# homeboard12.net
KiCad netlist of a schematic drawn in EAGLE
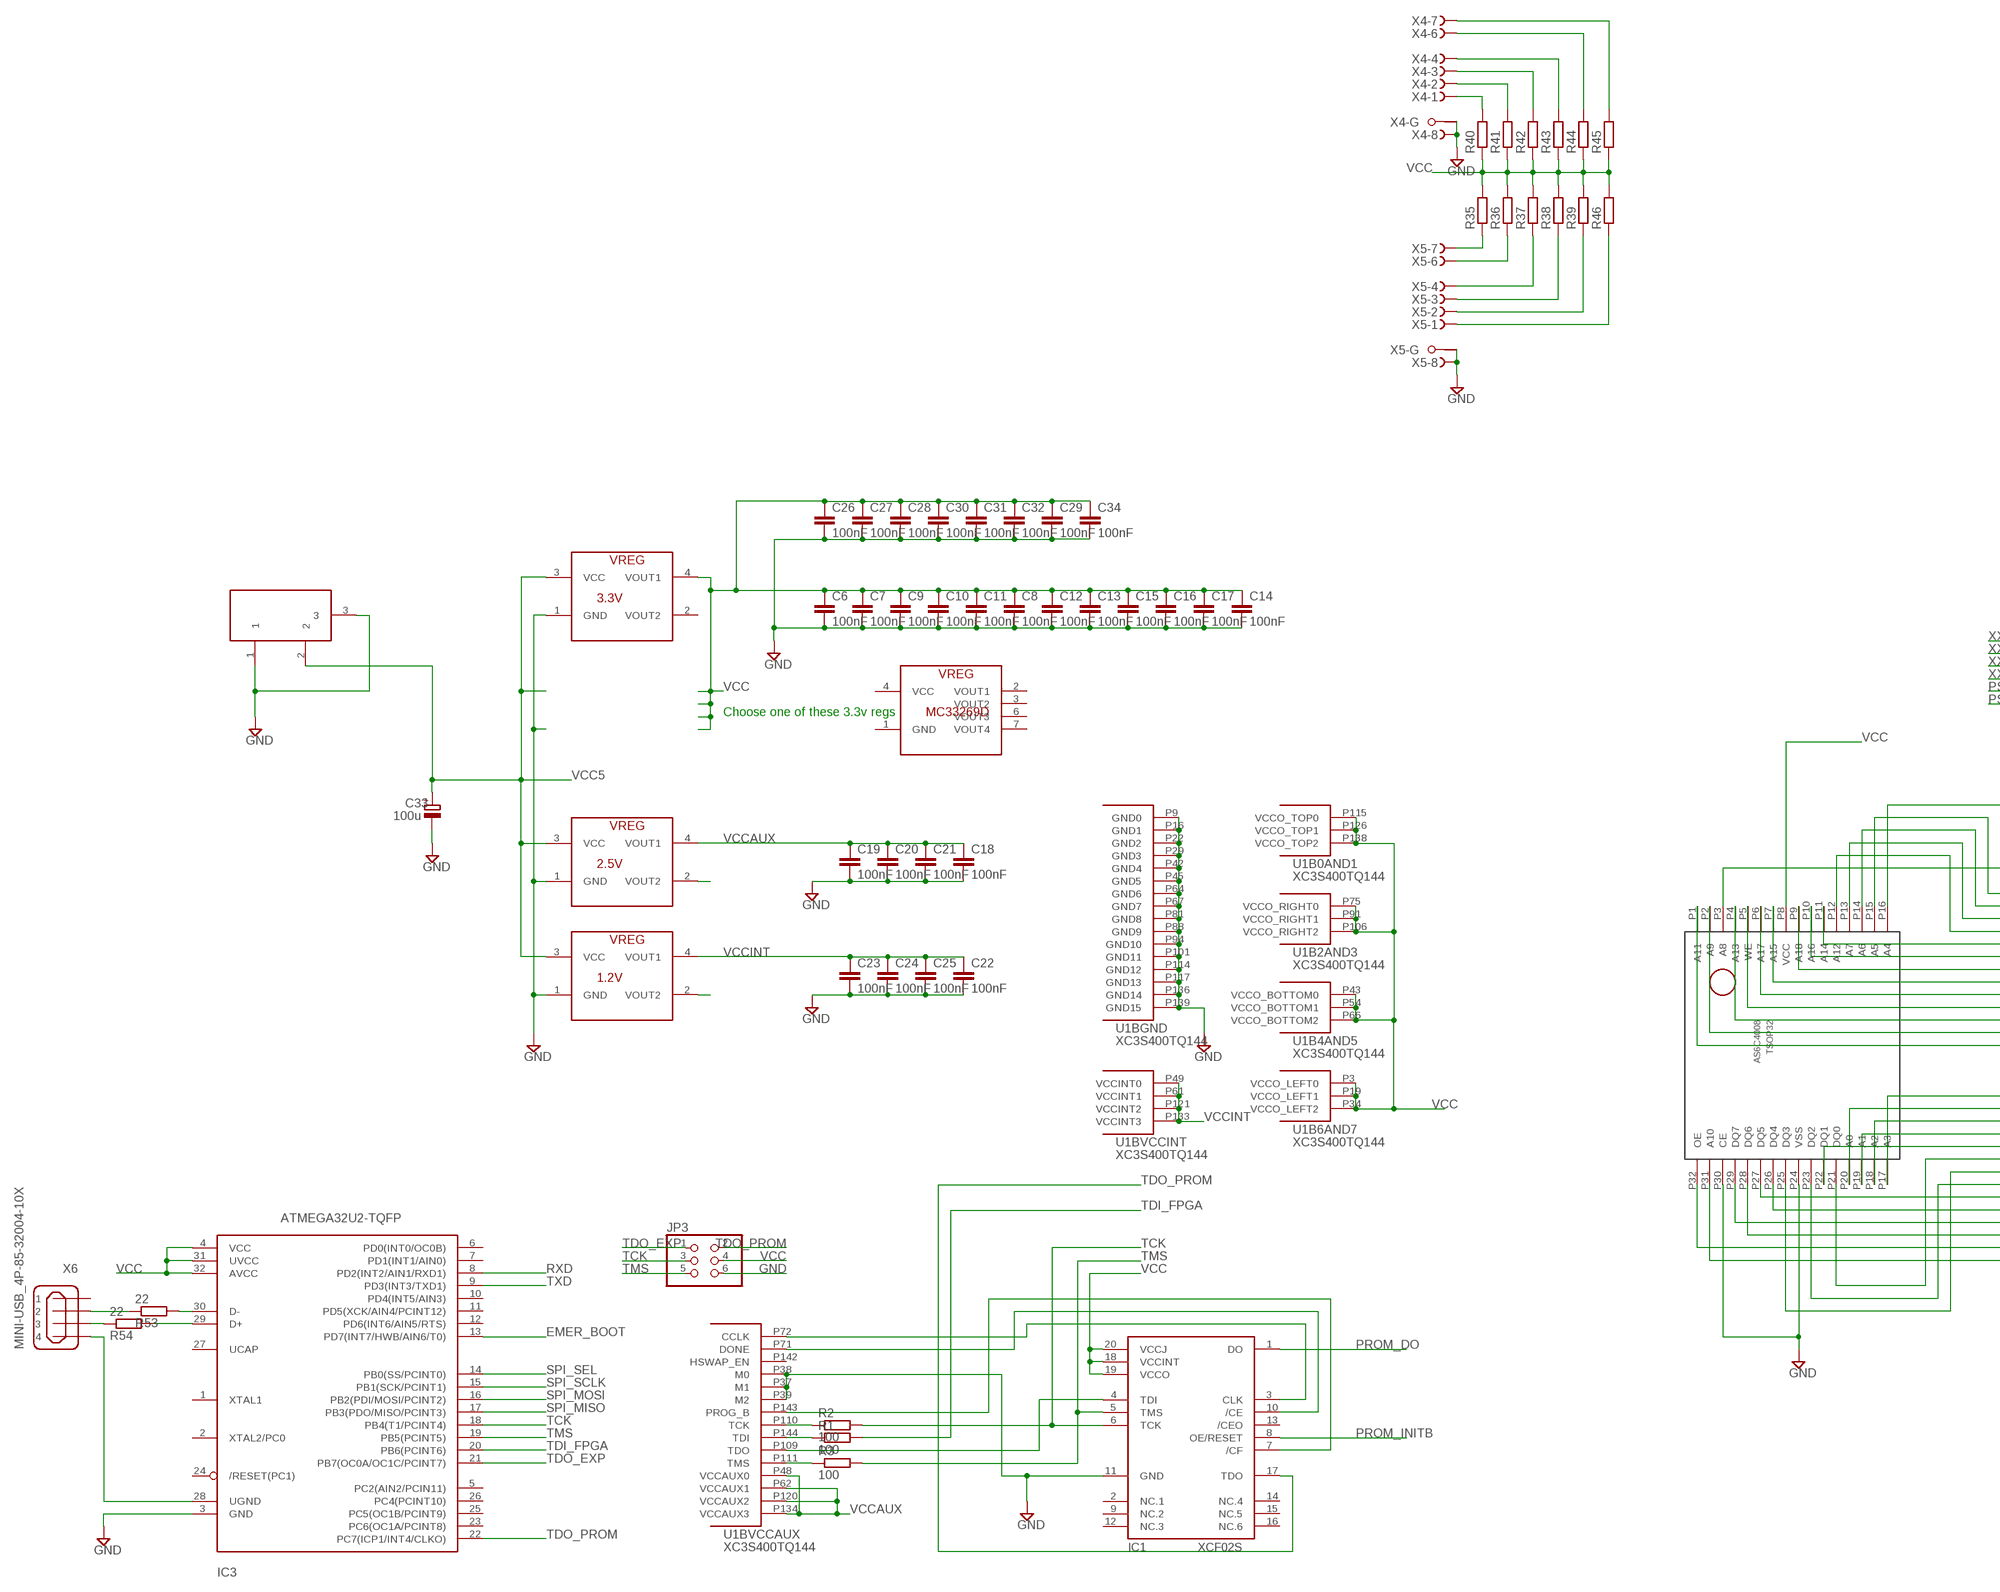
[diagram p0: schematic, sheet 1, part 1 of 3]
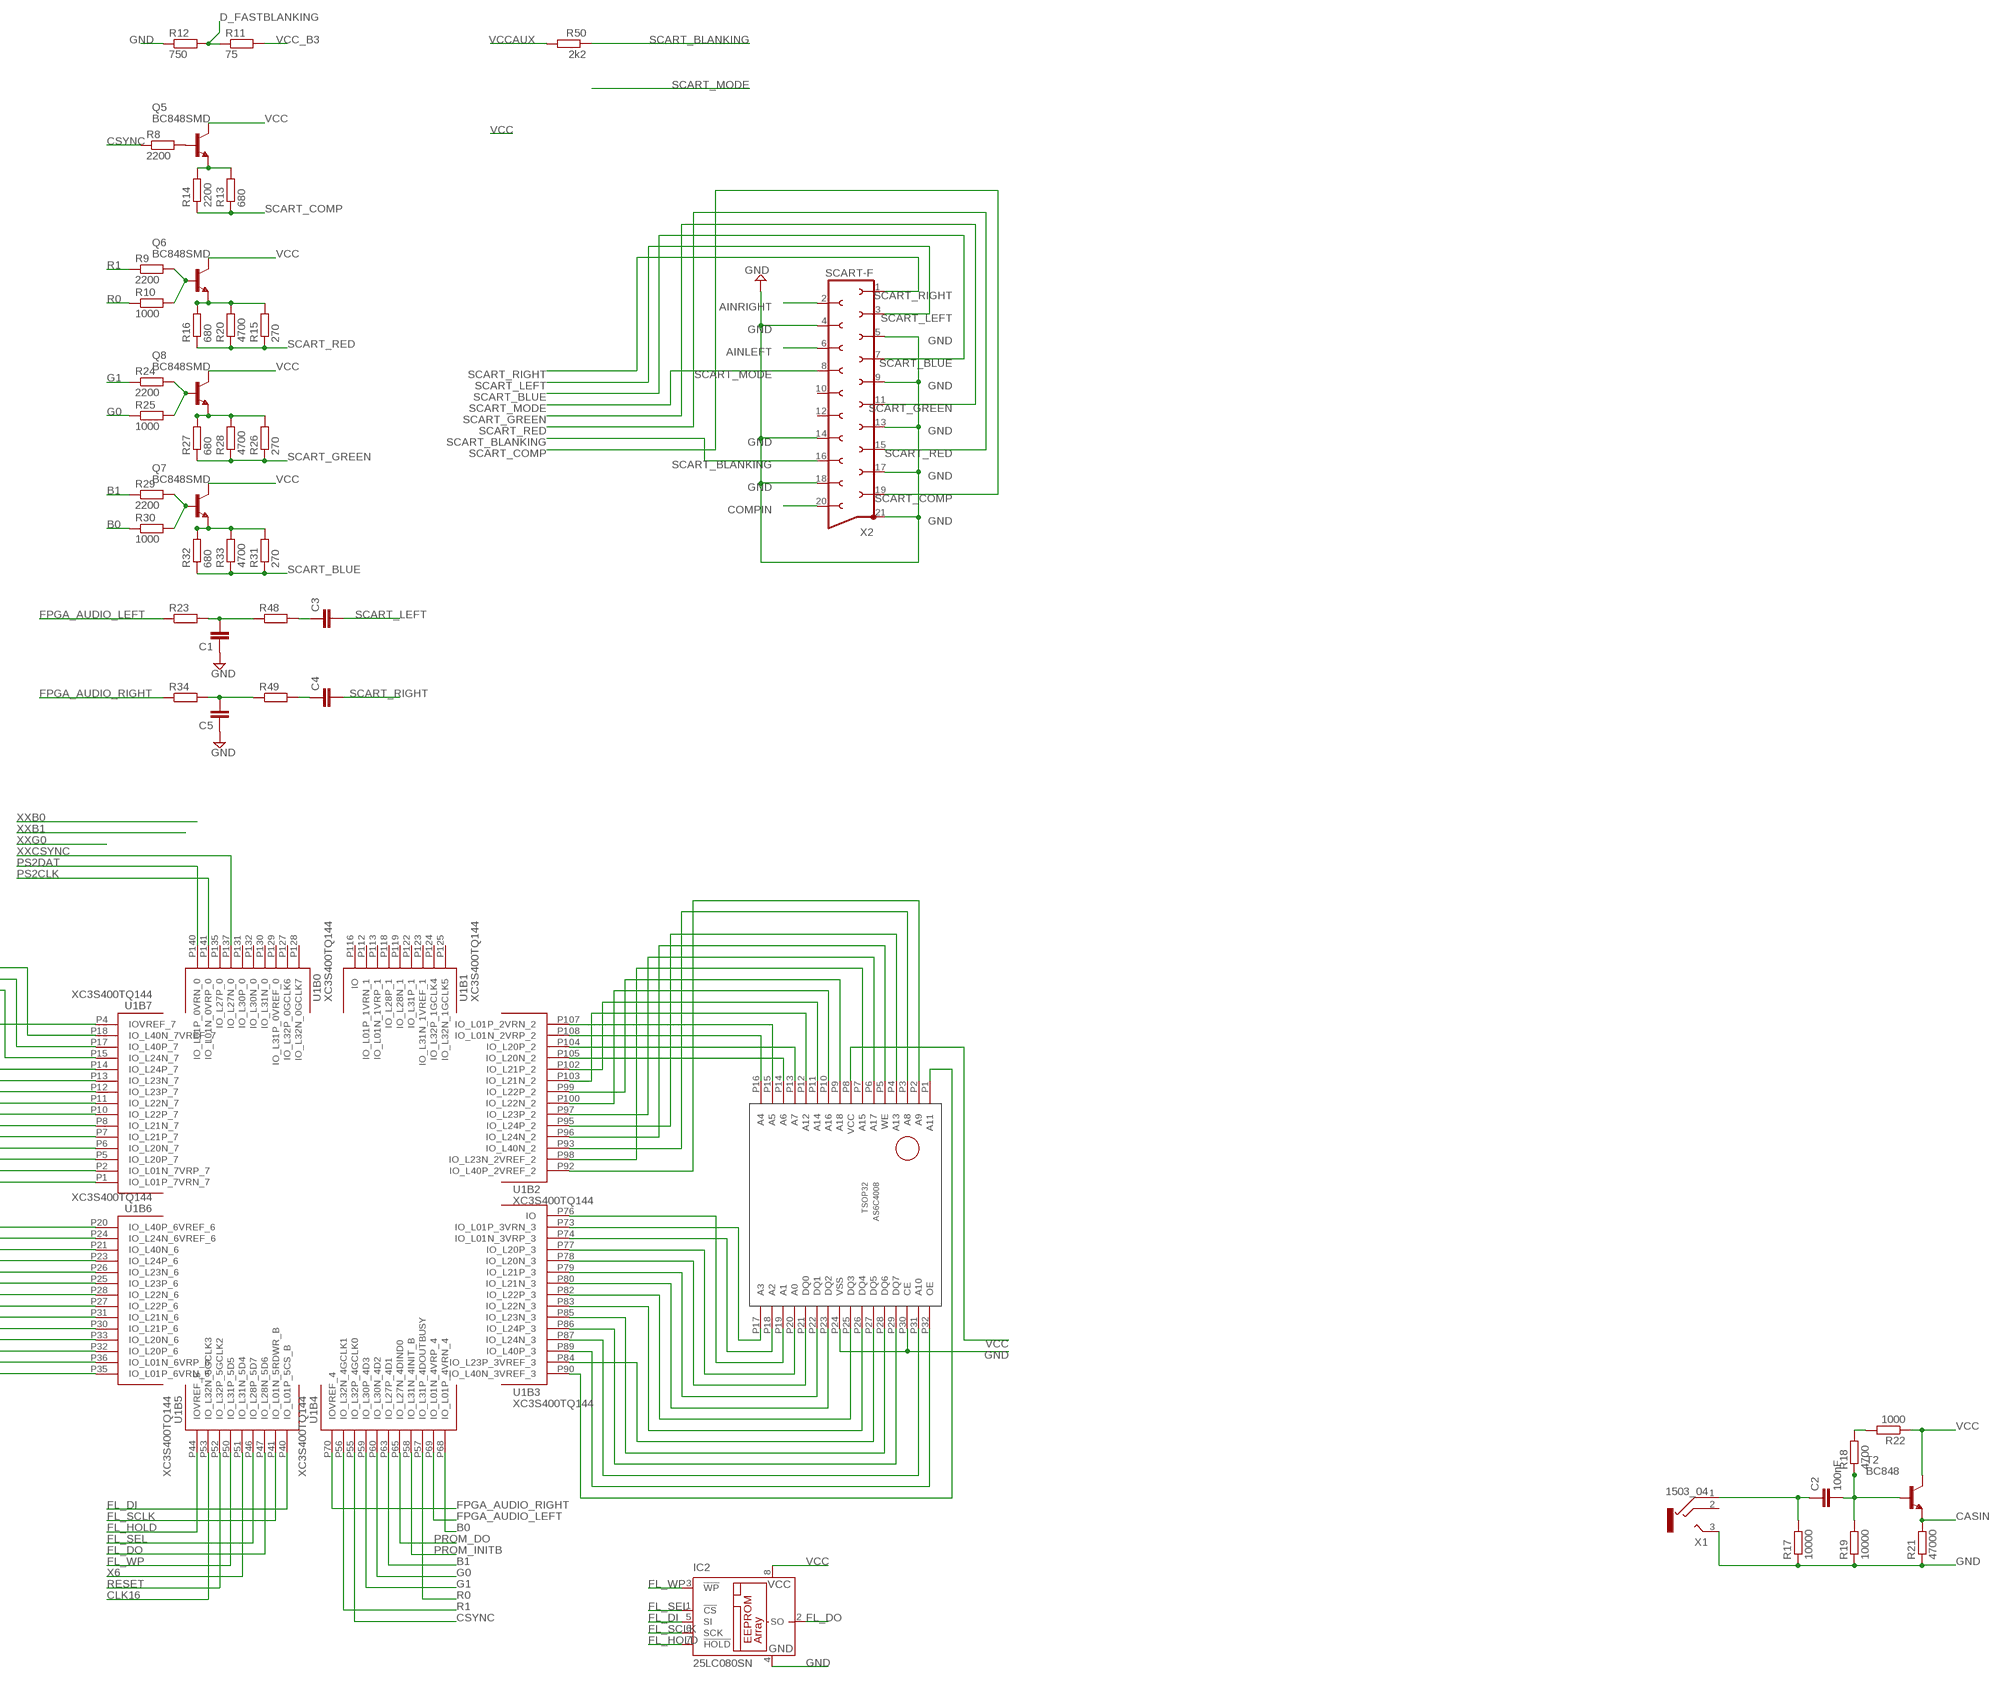
[diagram p1: schematic, sheet 1, part 2 of 3]
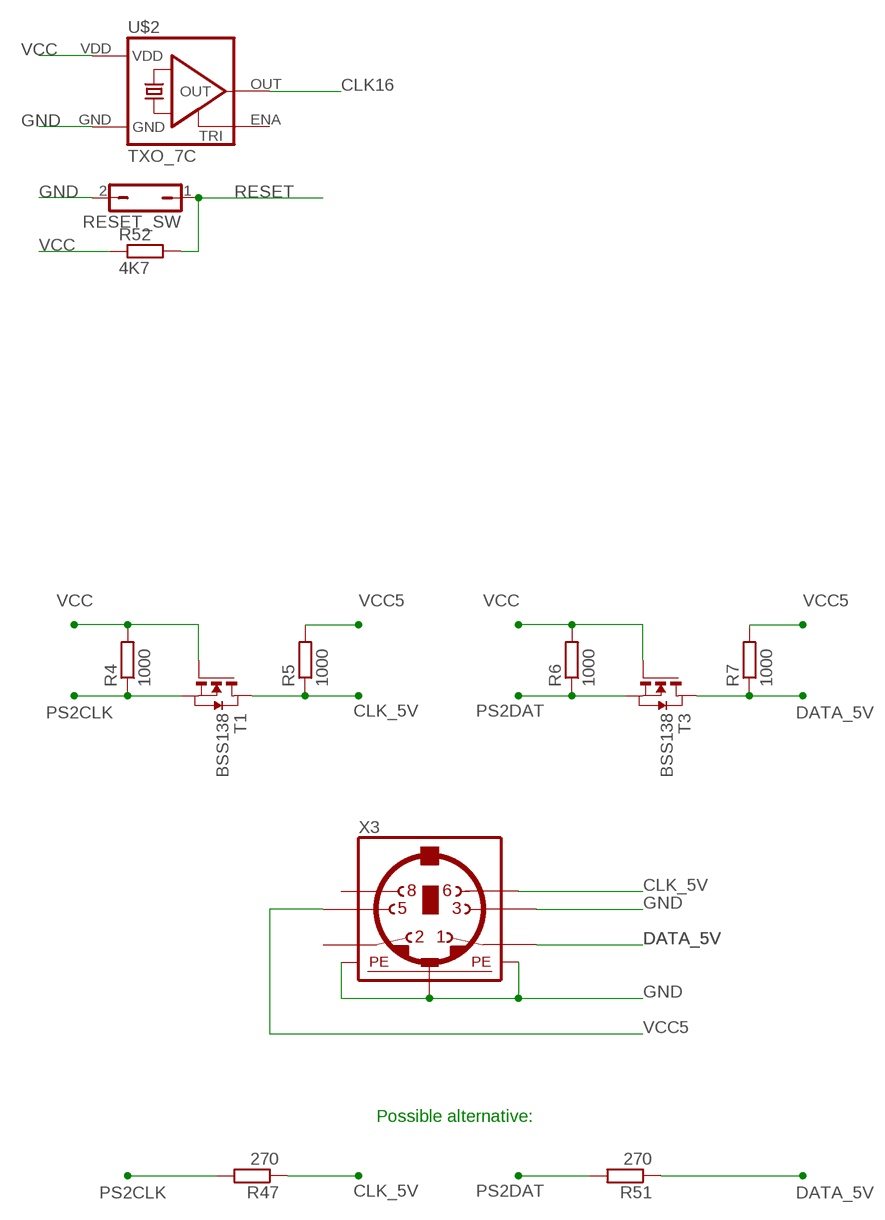
[diagram p2: schematic, sheet 1, part 3 of 3]

(export (version "E")
  (design (tool "Eeschema 10.0.6"))
  (components
    (comp (ref "C1")
      (value "C-EUC0603")
      (footprint "eagle-import:C0603")
      (libsource (lib "eagle-import") (part "resistor_C-EUC0603"))
    )
    (comp (ref "C2")
      (value "100nF")
      (footprint "eagle-import:C0603")
      (libsource (lib "eagle-import") (part "resistor_C-EUC0603"))
    )
    (comp (ref "C3")
      (value "C-EUC0603")
      (footprint "eagle-import:C0603")
      (libsource (lib "eagle-import") (part "resistor_C-EUC0603"))
    )
    (comp (ref "C4")
      (value "C-EUC0603")
      (footprint "eagle-import:C0603")
      (libsource (lib "eagle-import") (part "resistor_C-EUC0603"))
    )
    (comp (ref "C5")
      (value "C-EUC0603")
      (footprint "eagle-import:C0603")
      (libsource (lib "eagle-import") (part "resistor_C-EUC0603"))
    )
    (comp (ref "C6")
      (value "100nF")
      (footprint "eagle-import:C0603")
      (libsource (lib "eagle-import") (part "C-EUC0603"))
    )
    (comp (ref "C7")
      (value "100nF")
      (footprint "eagle-import:C0603")
      (libsource (lib "eagle-import") (part "C-EUC0603"))
    )
    (comp (ref "C8")
      (value "100nF")
      (footprint "eagle-import:C0603")
      (libsource (lib "eagle-import") (part "C-EUC0603"))
    )
    (comp (ref "C9")
      (value "100nF")
      (footprint "eagle-import:C0603")
      (libsource (lib "eagle-import") (part "C-EUC0603"))
    )
    (comp (ref "C10")
      (value "100nF")
      (footprint "eagle-import:C0603")
      (libsource (lib "eagle-import") (part "C-EUC0603"))
    )
    (comp (ref "C11")
      (value "100nF")
      (footprint "eagle-import:C0603")
      (libsource (lib "eagle-import") (part "C-EUC0603"))
    )
    (comp (ref "C12")
      (value "100nF")
      (footprint "eagle-import:C0603")
      (libsource (lib "eagle-import") (part "C-EUC0603"))
    )
    (comp (ref "C13")
      (value "100nF")
      (footprint "eagle-import:C0603")
      (libsource (lib "eagle-import") (part "C-EUC0603"))
    )
    (comp (ref "C14")
      (value "100nF")
      (footprint "eagle-import:C0603")
      (libsource (lib "eagle-import") (part "C-EUC0603"))
    )
    (comp (ref "C15")
      (value "100nF")
      (footprint "eagle-import:C0603")
      (libsource (lib "eagle-import") (part "C-EUC0603"))
    )
    (comp (ref "C16")
      (value "100nF")
      (footprint "eagle-import:C0603")
      (libsource (lib "eagle-import") (part "C-EUC0603"))
    )
    (comp (ref "C17")
      (value "100nF")
      (footprint "eagle-import:C0603")
      (libsource (lib "eagle-import") (part "C-EUC0603"))
    )
    (comp (ref "C18")
      (value "100nF")
      (footprint "eagle-import:C0603")
      (libsource (lib "eagle-import") (part "C-EUC0603"))
    )
    (comp (ref "C19")
      (value "100nF")
      (footprint "eagle-import:C0603")
      (libsource (lib "eagle-import") (part "C-EUC0603"))
    )
    (comp (ref "C20")
      (value "100nF")
      (footprint "eagle-import:C0603")
      (libsource (lib "eagle-import") (part "C-EUC0603"))
    )
    (comp (ref "C21")
      (value "100nF")
      (footprint "eagle-import:C0603")
      (libsource (lib "eagle-import") (part "C-EUC0603"))
    )
    (comp (ref "C22")
      (value "100nF")
      (footprint "eagle-import:C0603")
      (libsource (lib "eagle-import") (part "C-EUC0603"))
    )
    (comp (ref "C23")
      (value "100nF")
      (footprint "eagle-import:C0603")
      (libsource (lib "eagle-import") (part "C-EUC0603"))
    )
    (comp (ref "C24")
      (value "100nF")
      (footprint "eagle-import:C0603")
      (libsource (lib "eagle-import") (part "C-EUC0603"))
    )
    (comp (ref "C25")
      (value "100nF")
      (footprint "eagle-import:C0603")
      (libsource (lib "eagle-import") (part "C-EUC0603"))
    )
    (comp (ref "C26")
      (value "100nF")
      (footprint "eagle-import:C0603")
      (libsource (lib "eagle-import") (part "C-EUC0603"))
    )
    (comp (ref "C27")
      (value "100nF")
      (footprint "eagle-import:C0603")
      (libsource (lib "eagle-import") (part "C-EUC0603"))
    )
    (comp (ref "C28")
      (value "100nF")
      (footprint "eagle-import:C0603")
      (libsource (lib "eagle-import") (part "C-EUC0603"))
    )
    (comp (ref "C29")
      (value "100nF")
      (footprint "eagle-import:C0603")
      (libsource (lib "eagle-import") (part "C-EUC0603"))
    )
    (comp (ref "C30")
      (value "100nF")
      (footprint "eagle-import:C0603")
      (libsource (lib "eagle-import") (part "C-EUC0603"))
    )
    (comp (ref "C31")
      (value "100nF")
      (footprint "eagle-import:C0603")
      (libsource (lib "eagle-import") (part "C-EUC0603"))
    )
    (comp (ref "C32")
      (value "100nF")
      (footprint "eagle-import:C0603")
      (libsource (lib "eagle-import") (part "C-EUC0603"))
    )
    (comp (ref "C33")
      (value "100u")
      (footprint "eagle-import:PANASONIC_D")
      (libsource (lib "eagle-import") (part "CPOL-EUD"))
    )
    (comp (ref "C34")
      (value "100nF")
      (footprint "eagle-import:C0603")
      (libsource (lib "eagle-import") (part "C-EUC0603"))
    )
    (comp (ref "IC1")
      (value "XCF02S")
      (footprint "eagle-import:VO20")
      (libsource (lib "eagle-import") (part "XCF02S"))
    )
    (comp (ref "IC2")
      (value "25LC080SN")
      (footprint "eagle-import:SO-08")
      (fields (field (name "MF") "MICROCHIP") (field (name "MPN") "25LC080/SN"))
      (libsource (lib "eagle-import") (part "25SNLC080"))
    )
    (comp (ref "IC3")
      (value "ATMEGA32U2-TQFP")
      (footprint "eagle-import:TQFP32-08")
      (libsource (lib "eagle-import") (part "ATMEGA32U2-TQFP"))
    )
    (comp (ref "JP3")
      (value "PINHD-2X3")
      (footprint "eagle-import:2X03")
      (libsource (lib "eagle-import") (part "PINHD-2X3"))
    )
    (comp (ref "Q5")
      (value "BC848SMD")
      (footprint "eagle-import:SOT23")
      (libsource (lib "eagle-import") (part "BC848SMD"))
    )
    (comp (ref "Q6")
      (value "BC848SMD")
      (footprint "eagle-import:SOT23")
      (libsource (lib "eagle-import") (part "BC848SMD"))
    )
    (comp (ref "Q7")
      (value "BC848SMD")
      (footprint "eagle-import:SOT23")
      (libsource (lib "eagle-import") (part "BC848SMD"))
    )
    (comp (ref "Q8")
      (value "BC848SMD")
      (footprint "eagle-import:SOT23")
      (libsource (lib "eagle-import") (part "BC848SMD"))
    )
    (comp (ref "R1")
      (value "100")
      (footprint "eagle-import:R0805")
      (libsource (lib "eagle-import") (part "R-EU_R0805"))
    )
    (comp (ref "R2")
      (value "100")
      (footprint "eagle-import:R0805")
      (libsource (lib "eagle-import") (part "R-EU_R0805"))
    )
    (comp (ref "R3")
      (value "100")
      (footprint "eagle-import:R0805")
      (libsource (lib "eagle-import") (part "R-EU_R0805"))
    )
    (comp (ref "R4")
      (value "1000")
      (footprint "eagle-import:R0805")
      (libsource (lib "eagle-import") (part "R-EU_R0805"))
    )
    (comp (ref "R5")
      (value "1000")
      (footprint "eagle-import:R0805")
      (libsource (lib "eagle-import") (part "R-EU_R0805"))
    )
    (comp (ref "R6")
      (value "1000")
      (footprint "eagle-import:R0805")
      (libsource (lib "eagle-import") (part "R-EU_R0805"))
    )
    (comp (ref "R7")
      (value "1000")
      (footprint "eagle-import:R0805")
      (libsource (lib "eagle-import") (part "R-EU_R0805"))
    )
    (comp (ref "R8")
      (value "2200")
      (footprint "eagle-import:R0805")
      (libsource (lib "eagle-import") (part "R-EU_R0805"))
    )
    (comp (ref "R9")
      (value "2200")
      (footprint "eagle-import:R0805")
      (libsource (lib "eagle-import") (part "R-EU_R0805"))
    )
    (comp (ref "R10")
      (value "1000")
      (footprint "eagle-import:R0805")
      (libsource (lib "eagle-import") (part "R-EU_R0805"))
    )
    (comp (ref "R11")
      (value "75")
      (footprint "eagle-import:R0805")
      (libsource (lib "eagle-import") (part "R-EU_R0805"))
    )
    (comp (ref "R12")
      (value "750")
      (footprint "eagle-import:R0805")
      (libsource (lib "eagle-import") (part "R-EU_R0805"))
    )
    (comp (ref "R13")
      (value "680")
      (footprint "eagle-import:R0805")
      (libsource (lib "eagle-import") (part "R-EU_R0805"))
    )
    (comp (ref "R14")
      (value "2200")
      (footprint "eagle-import:R0805")
      (libsource (lib "eagle-import") (part "R-EU_R0805"))
    )
    (comp (ref "R15")
      (value "270")
      (footprint "eagle-import:R0805")
      (libsource (lib "eagle-import") (part "R-EU_R0805"))
    )
    (comp (ref "R16")
      (value "680")
      (footprint "eagle-import:R0805")
      (libsource (lib "eagle-import") (part "R-EU_R0805"))
    )
    (comp (ref "R17")
      (value "10000")
      (footprint "eagle-import:R0805")
      (libsource (lib "eagle-import") (part "R-EU_R0805"))
    )
    (comp (ref "R18")
      (value "4700")
      (footprint "eagle-import:R0805")
      (libsource (lib "eagle-import") (part "R-EU_R0805"))
    )
    (comp (ref "R19")
      (value "10000")
      (footprint "eagle-import:R0805")
      (libsource (lib "eagle-import") (part "R-EU_R0805"))
    )
    (comp (ref "R20")
      (value "4700")
      (footprint "eagle-import:R0805")
      (libsource (lib "eagle-import") (part "R-EU_R0805"))
    )
    (comp (ref "R21")
      (value "47000")
      (footprint "eagle-import:R0805")
      (libsource (lib "eagle-import") (part "R-EU_R0805"))
    )
    (comp (ref "R22")
      (value "1000")
      (footprint "eagle-import:R0805")
      (libsource (lib "eagle-import") (part "R-EU_R0805"))
    )
    (comp (ref "R23")
      (value "R-EU_M0805")
      (footprint "eagle-import:M0805")
      (libsource (lib "eagle-import") (part "resistor_R-EU_M0805"))
    )
    (comp (ref "R24")
      (value "2200")
      (footprint "eagle-import:R0805")
      (libsource (lib "eagle-import") (part "R-EU_R0805"))
    )
    (comp (ref "R25")
      (value "1000")
      (footprint "eagle-import:R0805")
      (libsource (lib "eagle-import") (part "R-EU_R0805"))
    )
    (comp (ref "R26")
      (value "270")
      (footprint "eagle-import:R0805")
      (libsource (lib "eagle-import") (part "R-EU_R0805"))
    )
    (comp (ref "R27")
      (value "680")
      (footprint "eagle-import:R0805")
      (libsource (lib "eagle-import") (part "R-EU_R0805"))
    )
    (comp (ref "R28")
      (value "4700")
      (footprint "eagle-import:R0805")
      (libsource (lib "eagle-import") (part "R-EU_R0805"))
    )
    (comp (ref "R29")
      (value "2200")
      (footprint "eagle-import:R0805")
      (libsource (lib "eagle-import") (part "R-EU_R0805"))
    )
    (comp (ref "R30")
      (value "1000")
      (footprint "eagle-import:R0805")
      (libsource (lib "eagle-import") (part "R-EU_R0805"))
    )
    (comp (ref "R31")
      (value "270")
      (footprint "eagle-import:R0805")
      (libsource (lib "eagle-import") (part "R-EU_R0805"))
    )
    (comp (ref "R32")
      (value "680")
      (footprint "eagle-import:R0805")
      (libsource (lib "eagle-import") (part "R-EU_R0805"))
    )
    (comp (ref "R33")
      (value "4700")
      (footprint "eagle-import:R0805")
      (libsource (lib "eagle-import") (part "R-EU_R0805"))
    )
    (comp (ref "R34")
      (value "R-EU_M0805")
      (footprint "eagle-import:M0805")
      (libsource (lib "eagle-import") (part "resistor_R-EU_M0805"))
    )
    (comp (ref "R35")
      (value "R-EU_M0805")
      (footprint "eagle-import:M0805")
      (libsource (lib "eagle-import") (part "resistor_R-EU_M0805"))
    )
    (comp (ref "R36")
      (value "R-EU_M0805")
      (footprint "eagle-import:M0805")
      (libsource (lib "eagle-import") (part "resistor_R-EU_M0805"))
    )
    (comp (ref "R37")
      (value "R-EU_M0805")
      (footprint "eagle-import:M0805")
      (libsource (lib "eagle-import") (part "resistor_R-EU_M0805"))
    )
    (comp (ref "R38")
      (value "R-EU_M0805")
      (footprint "eagle-import:M0805")
      (libsource (lib "eagle-import") (part "resistor_R-EU_M0805"))
    )
    (comp (ref "R39")
      (value "R-EU_M0805")
      (footprint "eagle-import:M0805")
      (libsource (lib "eagle-import") (part "resistor_R-EU_M0805"))
    )
    (comp (ref "R40")
      (value "R-EU_M0805")
      (footprint "eagle-import:M0805")
      (libsource (lib "eagle-import") (part "resistor_R-EU_M0805"))
    )
    (comp (ref "R41")
      (value "R-EU_M0805")
      (footprint "eagle-import:M0805")
      (libsource (lib "eagle-import") (part "resistor_R-EU_M0805"))
    )
    (comp (ref "R42")
      (value "R-EU_M0805")
      (footprint "eagle-import:M0805")
      (libsource (lib "eagle-import") (part "resistor_R-EU_M0805"))
    )
    (comp (ref "R43")
      (value "R-EU_M0805")
      (footprint "eagle-import:M0805")
      (libsource (lib "eagle-import") (part "resistor_R-EU_M0805"))
    )
    (comp (ref "R44")
      (value "R-EU_M0805")
      (footprint "eagle-import:M0805")
      (libsource (lib "eagle-import") (part "resistor_R-EU_M0805"))
    )
    (comp (ref "R45")
      (value "R-EU_M0805")
      (footprint "eagle-import:M0805")
      (libsource (lib "eagle-import") (part "resistor_R-EU_M0805"))
    )
    (comp (ref "R46")
      (value "R-EU_M0805")
      (footprint "eagle-import:M0805")
      (libsource (lib "eagle-import") (part "resistor_R-EU_M0805"))
    )
    (comp (ref "R47")
      (value "270")
      (footprint "eagle-import:R0805")
      (libsource (lib "eagle-import") (part "R-EU_R0805"))
    )
    (comp (ref "R48")
      (value "R-EU_M0805")
      (footprint "eagle-import:M0805")
      (libsource (lib "eagle-import") (part "resistor_R-EU_M0805"))
    )
    (comp (ref "R49")
      (value "R-EU_M0805")
      (footprint "eagle-import:M0805")
      (libsource (lib "eagle-import") (part "resistor_R-EU_M0805"))
    )
    (comp (ref "R50")
      (value "2k2")
      (footprint "eagle-import:M0805")
      (libsource (lib "eagle-import") (part "resistor_R-EU_M0805"))
    )
    (comp (ref "R51")
      (value "270")
      (footprint "eagle-import:R0805")
      (libsource (lib "eagle-import") (part "R-EU_R0805"))
    )
    (comp (ref "R52")
      (value "4K7")
      (footprint "eagle-import:M0805")
      (libsource (lib "eagle-import") (part "resistor_R-EU_M0805"))
    )
    (comp (ref "R53")
      (value "22")
      (footprint "eagle-import:R0805")
      (libsource (lib "eagle-import") (part "R-EU_R0805"))
    )
    (comp (ref "R54")
      (value "22")
      (footprint "eagle-import:R0805")
      (libsource (lib "eagle-import") (part "R-EU_R0805"))
    )
    (comp (ref "REG1.2")
      (value "1.2V")
      (footprint "eagle-import:SOT223")
      (libsource (lib "eagle-import") (part "NX1117"))
    )
    (comp (ref "REG2.5")
      (value "2.5V")
      (footprint "eagle-import:SOT223")
      (libsource (lib "eagle-import") (part "NX1117"))
    )
    (comp (ref "RESET_SW")
      (value "JP1Q")
      (footprint "eagle-import:JP1")
      (libsource (lib "eagle-import") (part "JP1Q"))
    )
    (comp (ref "T1")
      (value "BSS138")
      (footprint "eagle-import:SOT-23")
      (libsource (lib "eagle-import") (part "NMOSSOT23"))
    )
    (comp (ref "T2")
      (value "BC848")
      (footprint "eagle-import:SOT23")
      (libsource (lib "eagle-import") (part "BC848"))
    )
    (comp (ref "T3")
      (value "BSS138")
      (footprint "eagle-import:SOT-23")
      (libsource (lib "eagle-import") (part "NMOSSOT23"))
    )
    (comp (ref "U$1")
      (value "AS6C4008")
      (footprint "eagle-import:TSOP32")
      (libsource (lib "eagle-import") (part "AS6C4008"))
    )
    (comp (ref "U$2")
      (value "TXO_7C")
      (footprint "eagle-import:OSC_7C")
      (libsource (lib "eagle-import") (part "TXO_7C"))
    )
    (comp (ref "U$4")
      (value "3.3V")
      (footprint "eagle-import:SOT223")
      (libsource (lib "eagle-import") (part "NX1117"))
    )
    (comp (ref "U$5")
      (value "MC33269D")
      (footprint "eagle-import:SO8")
      (libsource (lib "eagle-import") (part "MC33269D"))
    )
    (comp (ref "U$6")
      (value "AS6C4008")
      (footprint "eagle-import:TSOP32")
      (libsource (lib "eagle-import") (part "AS6C4008"))
    )
    (comp (ref "U1")
      (value "XC3S400TQ144")
      (footprint "eagle-import:TQ144")
      (libsource (lib "eagle-import") (part "XC3S400TQ144"))
    )
    (comp (ref "X1")
      (value "1503_04")
      (footprint "eagle-import:1503_04")
      (libsource (lib "eagle-import") (part "1503_04"))
    )
    (comp (ref "X2")
      (value "SCART-F")
      (footprint "eagle-import:SCART-F")
      (libsource (lib "eagle-import") (part "SCART-F"))
    )
    (comp (ref "X3")
      (value "MINI_DIN_6")
      (footprint "eagle-import:M_DIN6")
      (libsource (lib "eagle-import") (part "MINI_DIN_6"))
    )
    (comp (ref "X4")
      (value "F09HPS")
      (footprint "eagle-import:F09HP")
      (libsource (lib "eagle-import") (part "F09HPS"))
    )
    (comp (ref "X5")
      (value "F09HPS")
      (footprint "eagle-import:F09HP")
      (libsource (lib "eagle-import") (part "F09HPS"))
    )
    (comp (ref "X6")
      (value "MINI-USB_4P-85-32004-10X")
      (footprint "eagle-import:85-32004-10X")
      (libsource (lib "eagle-import") (part "MINI-USB_4P-85-32004-10X"))
    )
    (comp (ref "X8")
      (value "DC21MMX")
      (footprint "eagle-import:DC-21MM")
      (libsource (lib "eagle-import") (part "DC21MMX"))
    )
  )
  (nets
    (net (code "1") (name "/AINLEFT") (class "Default")
      (node (ref "X2") (pin "6") (pinfunction "6_6") (pintype "passive"))
    )
    (net (code "2") (name "/AINRIGHT") (class "Default")
      (node (ref "X2") (pin "2") (pinfunction "2_2") (pintype "passive"))
    )
    (net (code "3") (name "/B0") (class "Default")
      (node (ref "R30") (pin "1") (pinfunction "1_1") (pintype "passive"))
      (node (ref "U1") (pin "P68") (pinfunction "IO_L01P_4VRN_4_P68") (pintype "bidirectional"))
    )
    (net (code "4") (name "/B1") (class "Default")
      (node (ref "R29") (pin "1") (pinfunction "1_1") (pintype "passive"))
      (node (ref "U1") (pin "P63") (pinfunction "IO_L27P_4D1_P63") (pintype "bidirectional"))
    )
    (net (code "5") (name "/CASIN") (class "Default")
      (node (ref "R21") (pin "2") (pinfunction "2_2") (pintype "passive"))
      (node (ref "T2") (pin "2") (pinfunction "E_2") (pintype "passive"))
    )
    (net (code "6") (name "/CLK16") (class "Default")
      (node (ref "U$2") (pin "OUT") (pinfunction "OUT_OUT") (pintype "output"))
      (node (ref "U1") (pin "P53") (pinfunction "IO_L32N_5GCLK3_P53") (pintype "bidirectional"))
    )
    (net (code "7") (name "/CLK_5V") (class "Default")
      (node (ref "R47") (pin "1") (pinfunction "1_1") (pintype "passive"))
      (node (ref "R5") (pin "1") (pinfunction "1_1") (pintype "passive"))
      (node (ref "T1") (pin "1") (pinfunction "D_1") (pintype "passive"))
      (node (ref "X3") (pin "6") (pinfunction "6_6") (pintype "passive"))
    )
    (net (code "8") (name "/COMPIN") (class "Default")
      (node (ref "X2") (pin "20") (pinfunction "20_20") (pintype "passive"))
    )
    (net (code "9") (name "/CSYNC") (class "Default")
      (node (ref "R8") (pin "1") (pinfunction "1_1") (pintype "passive"))
      (node (ref "U1") (pin "P55") (pinfunction "IO_L32P_4GCLK0_P55") (pintype "bidirectional"))
    )
    (net (code "10") (name "/DATA_5V") (class "Default")
      (node (ref "R51") (pin "1") (pinfunction "1_1") (pintype "passive"))
      (node (ref "R7") (pin "1") (pinfunction "1_1") (pintype "passive"))
      (node (ref "T3") (pin "1") (pinfunction "D_1") (pintype "passive"))
      (node (ref "X3") (pin "1") (pinfunction "1_1") (pintype "passive"))
    )
    (net (code "11") (name "/D_FASTBLANKING") (class "Default")
      (node (ref "R11") (pin "1") (pinfunction "1_1") (pintype "passive"))
      (node (ref "R12") (pin "2") (pinfunction "2_2") (pintype "passive"))
    )
    (net (code "12") (name "/EMER_BOOT") (class "Default")
      (node (ref "IC3") (pin "13") (pinfunction "PD7(INT7/HWB/AIN6/T0)_13") (pintype "bidirectional"))
    )
    (net (code "13") (name "/FL_DI") (class "Default")
      (node (ref "IC2") (pin "5") (pinfunction "SI_5") (pintype "input"))
      (node (ref "U1") (pin "P40") (pinfunction "IO_L01P_5CS_B_P40") (pintype "bidirectional"))
    )
    (net (code "14") (name "/FL_DO") (class "Default")
      (node (ref "IC2") (pin "2") (pinfunction "SO_2") (pintype "bidirectional"))
      (node (ref "U1") (pin "P47") (pinfunction "IO_L28N_5D6_P47") (pintype "bidirectional"))
    )
    (net (code "15") (name "/FL_HOLD") (class "Default")
      (node (ref "IC2") (pin "7") (pinfunction "~{HOLD}_7") (pintype "input"))
      (node (ref "U1") (pin "P44") (pinfunction "IOVREF_5_P44") (pintype "bidirectional"))
    )
    (net (code "16") (name "/FL_SCLK") (class "Default")
      (node (ref "IC2") (pin "6") (pinfunction "SCK_6") (pintype "input"))
      (node (ref "U1") (pin "P41") (pinfunction "IO_L01N_5RDWR_B_P41") (pintype "bidirectional"))
    )
    (net (code "17") (name "/FL_SEL") (class "Default")
      (node (ref "IC2") (pin "1") (pinfunction "~{CS}_1") (pintype "input"))
      (node (ref "U1") (pin "P46") (pinfunction "IO_L28P_5D7_P46") (pintype "bidirectional"))
    )
    (net (code "18") (name "/FL_WP") (class "Default")
      (node (ref "IC2") (pin "3") (pinfunction "~{WP}_3") (pintype "input"))
      (node (ref "U1") (pin "P50") (pinfunction "IO_L31P_5D5_P50") (pintype "bidirectional"))
    )
    (net (code "19") (name "/FPGA_AUDIO_LEFT") (class "Default")
      (node (ref "R23") (pin "1") (pinfunction "1_1") (pintype "passive"))
      (node (ref "U1") (pin "P69") (pinfunction "IO_L01N_4VRP_4_P69") (pintype "bidirectional"))
    )
    (net (code "20") (name "/FPGA_AUDIO_RIGHT") (class "Default")
      (node (ref "R34") (pin "1") (pinfunction "1_1") (pintype "passive"))
      (node (ref "U1") (pin "P70") (pinfunction "IOVREF_4_P70") (pintype "bidirectional"))
    )
    (net (code "21") (name "/G0") (class "Default")
      (node (ref "R25") (pin "1") (pinfunction "1_1") (pintype "passive"))
      (node (ref "U1") (pin "P60") (pinfunction "IO_L30N_4D2_P60") (pintype "bidirectional"))
    )
    (net (code "22") (name "/G1") (class "Default")
      (node (ref "R24") (pin "1") (pinfunction "1_1") (pintype "passive"))
      (node (ref "U1") (pin "P59") (pinfunction "IO_L30P_4D3_P59") (pintype "bidirectional"))
    )
    (net (code "23") (name "/PROM_DO") (class "Default")
      (node (ref "IC1") (pin "1") (pinfunction "DO_1") (pintype "bidirectional"))
      (node (ref "U1") (pin "P65") (pinfunction "IO_L27N_4DIND0_P65") (pintype "bidirectional"))
    )
    (net (code "24") (name "/PROM_INITB") (class "Default")
      (node (ref "IC1") (pin "8") (pinfunction "OE/RESET_8") (pintype "bidirectional"))
      (node (ref "U1") (pin "P58") (pinfunction "IO_L31N_4INIT_B_P58") (pintype "bidirectional"))
    )
    (net (code "25") (name "/PS2CLK") (class "Default")
      (node (ref "R4") (pin "1") (pinfunction "1_1") (pintype "passive"))
      (node (ref "R47") (pin "2") (pinfunction "2_2") (pintype "passive"))
      (node (ref "T1") (pin "2") (pinfunction "S_2") (pintype "passive"))
      (node (ref "U1") (pin "P141") (pinfunction "IO_L01N_0VRP_0_P141") (pintype "bidirectional"))
    )
    (net (code "26") (name "/PS2DAT") (class "Default")
      (node (ref "R51") (pin "2") (pinfunction "2_2") (pintype "passive"))
      (node (ref "R6") (pin "1") (pinfunction "1_1") (pintype "passive"))
      (node (ref "T3") (pin "2") (pinfunction "S_2") (pintype "passive"))
      (node (ref "U1") (pin "P140") (pinfunction "IO_L01P_0VRN_0_P140") (pintype "bidirectional"))
    )
    (net (code "27") (name "/R0") (class "Default")
      (node (ref "R10") (pin "1") (pinfunction "1_1") (pintype "passive"))
      (node (ref "U1") (pin "P57") (pinfunction "IO_L31P_4DOUTBUSY_P57") (pintype "bidirectional"))
    )
    (net (code "28") (name "/R1") (class "Default")
      (node (ref "R9") (pin "1") (pinfunction "1_1") (pintype "passive"))
      (node (ref "U1") (pin "P56") (pinfunction "IO_L32N_4GCLK1_P56") (pintype "bidirectional"))
    )
    (net (code "29") (name "/RESET") (class "Default")
      (node (ref "R52") (pin "2") (pinfunction "2_2") (pintype "passive"))
      (node (ref "RESET_SW") (pin "1") (pinfunction "1_1") (pintype "passive"))
      (node (ref "U1") (pin "P52") (pinfunction "IO_L32P_5GCLK2_P52") (pintype "bidirectional"))
    )
    (net (code "30") (name "/RXD") (class "Default")
      (node (ref "IC3") (pin "8") (pinfunction "PD2(INT2/AIN1/RXD1)_8") (pintype "bidirectional"))
    )
    (net (code "31") (name "/SCART_BLANKING") (class "Default")
      (node (ref "R50") (pin "1") (pinfunction "1_1") (pintype "passive"))
      (node (ref "X2") (pin "16") (pinfunction "16_16") (pintype "passive"))
    )
    (net (code "32") (name "/SCART_BLUE") (class "Default")
      (node (ref "R31") (pin "1") (pinfunction "1_1") (pintype "passive"))
      (node (ref "R32") (pin "1") (pinfunction "1_1") (pintype "passive"))
      (node (ref "R33") (pin "1") (pinfunction "1_1") (pintype "passive"))
      (node (ref "X2") (pin "7") (pinfunction "7_7") (pintype "passive"))
    )
    (net (code "33") (name "/SCART_COMP") (class "Default")
      (node (ref "R13") (pin "1") (pinfunction "1_1") (pintype "passive"))
      (node (ref "R14") (pin "1") (pinfunction "1_1") (pintype "passive"))
      (node (ref "X2") (pin "19") (pinfunction "19_19") (pintype "passive"))
    )
    (net (code "34") (name "/SCART_GREEN") (class "Default")
      (node (ref "R26") (pin "1") (pinfunction "1_1") (pintype "passive"))
      (node (ref "R27") (pin "1") (pinfunction "1_1") (pintype "passive"))
      (node (ref "R28") (pin "1") (pinfunction "1_1") (pintype "passive"))
      (node (ref "X2") (pin "11") (pinfunction "11_11") (pintype "passive"))
    )
    (net (code "35") (name "/SCART_LEFT") (class "Default")
      (node (ref "C3") (pin "2") (pinfunction "2_2") (pintype "passive"))
      (node (ref "X2") (pin "3") (pinfunction "3_3") (pintype "passive"))
    )
    (net (code "36") (name "/SCART_MODE") (class "Default")
      (node (ref "X2") (pin "8") (pinfunction "8_8") (pintype "passive"))
    )
    (net (code "37") (name "/SCART_RED") (class "Default")
      (node (ref "R15") (pin "1") (pinfunction "1_1") (pintype "passive"))
      (node (ref "R16") (pin "1") (pinfunction "1_1") (pintype "passive"))
      (node (ref "R20") (pin "1") (pinfunction "1_1") (pintype "passive"))
      (node (ref "X2") (pin "15") (pinfunction "15_15") (pintype "passive"))
    )
    (net (code "38") (name "/SCART_RIGHT") (class "Default")
      (node (ref "C4") (pin "2") (pinfunction "2_2") (pintype "passive"))
      (node (ref "X2") (pin "1") (pinfunction "1_1") (pintype "passive"))
    )
    (net (code "39") (name "/SPI_MISO") (class "Default")
      (node (ref "IC3") (pin "17") (pinfunction "PB3(PDO/MISO/PCINT3)_17") (pintype "bidirectional"))
    )
    (net (code "40") (name "/SPI_MOSI") (class "Default")
      (node (ref "IC3") (pin "16") (pinfunction "PB2(PDI/MOSI/PCINT2)_16") (pintype "bidirectional"))
    )
    (net (code "41") (name "/SPI_SCLK") (class "Default")
      (node (ref "IC3") (pin "15") (pinfunction "PB1(SCK/PCINT1)_15") (pintype "bidirectional"))
    )
    (net (code "42") (name "/SPI_SEL") (class "Default")
      (node (ref "IC3") (pin "14") (pinfunction "PB0(SS/PCINT0)_14") (pintype "bidirectional"))
    )
    (net (code "43") (name "/TCK") (class "Default")
      (node (ref "IC1") (pin "6") (pinfunction "TCK_6") (pintype "bidirectional"))
      (node (ref "IC3") (pin "18") (pinfunction "PB4(T1/PCINT4)_18") (pintype "bidirectional"))
      (node (ref "JP3") (pin "3") (pinfunction "3_3") (pintype "passive"))
      (node (ref "R2") (pin "2") (pinfunction "2_2") (pintype "passive"))
    )
    (net (code "44") (name "/TDI_FPGA") (class "Default")
      (node (ref "IC3") (pin "20") (pinfunction "PB6(PCINT6)_20") (pintype "bidirectional"))
      (node (ref "R1") (pin "2") (pinfunction "2_2") (pintype "passive"))
    )
    (net (code "45") (name "/TDO_EXP") (class "Default")
      (node (ref "IC3") (pin "21") (pinfunction "PB7(OC0A/OC1C/PCINT7)_21") (pintype "bidirectional"))
      (node (ref "JP3") (pin "1") (pinfunction "1_1") (pintype "passive"))
    )
    (net (code "46") (name "/TDO_PROM") (class "Default")
      (node (ref "IC1") (pin "17") (pinfunction "TDO_17") (pintype "bidirectional"))
      (node (ref "IC3") (pin "22") (pinfunction "PC7(ICP1/INT4/CLKO)_22") (pintype "bidirectional"))
      (node (ref "JP3") (pin "2") (pinfunction "2_2") (pintype "passive"))
    )
    (net (code "47") (name "/TMS") (class "Default")
      (node (ref "IC1") (pin "5") (pinfunction "TMS_5") (pintype "bidirectional"))
      (node (ref "IC3") (pin "19") (pinfunction "PB5(PCINT5)_19") (pintype "bidirectional"))
      (node (ref "JP3") (pin "5") (pinfunction "5_5") (pintype "passive"))
      (node (ref "R3") (pin "2") (pinfunction "2_2") (pintype "passive"))
    )
    (net (code "48") (name "/TXD") (class "Default")
      (node (ref "IC3") (pin "9") (pinfunction "PD3(INT3/TXD1)_9") (pintype "bidirectional"))
    )
    (net (code "49") (name "/VCC") (class "Default")
      (node (ref "C10") (pin "1") (pinfunction "1_1") (pintype "passive"))
      (node (ref "C11") (pin "1") (pinfunction "1_1") (pintype "passive"))
      (node (ref "C12") (pin "1") (pinfunction "1_1") (pintype "passive"))
      (node (ref "C13") (pin "1") (pinfunction "1_1") (pintype "passive"))
      (node (ref "C14") (pin "1") (pinfunction "1_1") (pintype "passive"))
      (node (ref "C15") (pin "1") (pinfunction "1_1") (pintype "passive"))
      (node (ref "C16") (pin "1") (pinfunction "1_1") (pintype "passive"))
      (node (ref "C17") (pin "1") (pinfunction "1_1") (pintype "passive"))
      (node (ref "C26") (pin "1") (pinfunction "1_1") (pintype "passive"))
      (node (ref "C27") (pin "1") (pinfunction "1_1") (pintype "passive"))
      (node (ref "C28") (pin "1") (pinfunction "1_1") (pintype "passive"))
      (node (ref "C29") (pin "1") (pinfunction "1_1") (pintype "passive"))
      (node (ref "C30") (pin "1") (pinfunction "1_1") (pintype "passive"))
      (node (ref "C31") (pin "1") (pinfunction "1_1") (pintype "passive"))
      (node (ref "C32") (pin "1") (pinfunction "1_1") (pintype "passive"))
      (node (ref "C34") (pin "1") (pinfunction "1_1") (pintype "passive"))
      (node (ref "C6") (pin "1") (pinfunction "1_1") (pintype "passive"))
      (node (ref "C7") (pin "1") (pinfunction "1_1") (pintype "passive"))
      (node (ref "C8") (pin "1") (pinfunction "1_1") (pintype "passive"))
      (node (ref "C9") (pin "1") (pinfunction "1_1") (pintype "passive"))
      (node (ref "IC1") (pin "18") (pinfunction "VCCINT_18") (pintype "bidirectional"))
      (node (ref "IC1") (pin "19") (pinfunction "VCCO_19") (pintype "bidirectional"))
      (node (ref "IC1") (pin "20") (pinfunction "VCCJ_20") (pintype "bidirectional"))
      (node (ref "IC2") (pin "8") (pinfunction "VCC_8") (pintype "power_in"))
      (node (ref "IC3") (pin "31") (pinfunction "UVCC_31") (pintype "bidirectional"))
      (node (ref "IC3") (pin "32") (pinfunction "AVCC_32") (pintype "bidirectional"))
      (node (ref "IC3") (pin "4") (pinfunction "VCC_4") (pintype "bidirectional"))
      (node (ref "JP3") (pin "4") (pinfunction "4_4") (pintype "passive"))
      (node (ref "Q5") (pin "3") (pinfunction "C_3") (pintype "passive"))
      (node (ref "Q6") (pin "3") (pinfunction "C_3") (pintype "passive"))
      (node (ref "Q7") (pin "3") (pinfunction "C_3") (pintype "passive"))
      (node (ref "Q8") (pin "3") (pinfunction "C_3") (pintype "passive"))
      (node (ref "R22") (pin "1") (pinfunction "1_1") (pintype "passive"))
      (node (ref "R35") (pin "2") (pinfunction "2_2") (pintype "passive"))
      (node (ref "R36") (pin "2") (pinfunction "2_2") (pintype "passive"))
      (node (ref "R37") (pin "2") (pinfunction "2_2") (pintype "passive"))
      (node (ref "R38") (pin "2") (pinfunction "2_2") (pintype "passive"))
      (node (ref "R39") (pin "2") (pinfunction "2_2") (pintype "passive"))
      (node (ref "R4") (pin "2") (pinfunction "2_2") (pintype "passive"))
      (node (ref "R40") (pin "1") (pinfunction "1_1") (pintype "passive"))
      (node (ref "R41") (pin "1") (pinfunction "1_1") (pintype "passive"))
      (node (ref "R42") (pin "1") (pinfunction "1_1") (pintype "passive"))
      (node (ref "R43") (pin "1") (pinfunction "1_1") (pintype "passive"))
      (node (ref "R44") (pin "1") (pinfunction "1_1") (pintype "passive"))
      (node (ref "R45") (pin "1") (pinfunction "1_1") (pintype "passive"))
      (node (ref "R46") (pin "2") (pinfunction "2_2") (pintype "passive"))
      (node (ref "R52") (pin "1") (pinfunction "1_1") (pintype "passive"))
      (node (ref "R6") (pin "2") (pinfunction "2_2") (pintype "passive"))
      (node (ref "T1") (pin "3") (pinfunction "G_3") (pintype "passive"))
      (node (ref "T2") (pin "3") (pinfunction "C_3") (pintype "passive"))
      (node (ref "T3") (pin "3") (pinfunction "G_3") (pintype "passive"))
      (node (ref "U$1") (pin "P8") (pinfunction "VCC_P8") (pintype "bidirectional"))
      (node (ref "U$2") (pin "VDD") (pinfunction "VDD_VDD") (pintype "power_in"))
      (node (ref "U$4") (pin "4") (pinfunction "VOUT1_4") (pintype "bidirectional"))
      (node (ref "U$6") (pin "P8") (pinfunction "VCC_P8") (pintype "bidirectional"))
      (node (ref "U1") (pin "P106") (pinfunction "VCCO_RIGHT2_P106") (pintype "passive"))
      (node (ref "U1") (pin "P115") (pinfunction "VCCO_TOP0_P115") (pintype "passive"))
      (node (ref "U1") (pin "P126") (pinfunction "VCCO_TOP1_P126") (pintype "passive"))
      (node (ref "U1") (pin "P138") (pinfunction "VCCO_TOP2_P138") (pintype "passive"))
      (node (ref "U1") (pin "P19") (pinfunction "VCCO_LEFT1_P19") (pintype "passive"))
      (node (ref "U1") (pin "P3") (pinfunction "VCCO_LEFT0_P3") (pintype "passive"))
      (node (ref "U1") (pin "P34") (pinfunction "VCCO_LEFT2_P34") (pintype "passive"))
      (node (ref "U1") (pin "P43") (pinfunction "VCCO_BOTTOM0_P43") (pintype "passive"))
      (node (ref "U1") (pin "P54") (pinfunction "VCCO_BOTTOM1_P54") (pintype "passive"))
      (node (ref "U1") (pin "P66") (pinfunction "VCCO_BOTTOM2_P66") (pintype "passive"))
      (node (ref "U1") (pin "P75") (pinfunction "VCCO_RIGHT0_P75") (pintype "passive"))
      (node (ref "U1") (pin "P91") (pinfunction "VCCO_RIGHT1_P91") (pintype "passive"))
    )
    (net (code "50") (name "/VCC5") (class "Default")
      (node (ref "C33") (pin "+") (pinfunction "+_+") (pintype "passive"))
      (node (ref "R5") (pin "2") (pinfunction "2_2") (pintype "passive"))
      (node (ref "R7") (pin "2") (pinfunction "2_2") (pintype "passive"))
      (node (ref "REG1.2") (pin "3") (pinfunction "VCC_3") (pintype "bidirectional"))
      (node (ref "REG2.5") (pin "3") (pinfunction "VCC_3") (pintype "bidirectional"))
      (node (ref "U$4") (pin "3") (pinfunction "VCC_3") (pintype "bidirectional"))
      (node (ref "X3") (pin "5") (pinfunction "5_5") (pintype "passive"))
      (node (ref "X8") (pin "2") (pinfunction "2_2") (pintype "power_in"))
    )
    (net (code "51") (name "/VCCAUX") (class "Default")
      (node (ref "C18") (pin "1") (pinfunction "1_1") (pintype "passive"))
      (node (ref "C19") (pin "1") (pinfunction "1_1") (pintype "passive"))
      (node (ref "C20") (pin "1") (pinfunction "1_1") (pintype "passive"))
      (node (ref "C21") (pin "1") (pinfunction "1_1") (pintype "passive"))
      (node (ref "R50") (pin "2") (pinfunction "2_2") (pintype "passive"))
      (node (ref "REG2.5") (pin "4") (pinfunction "VOUT1_4") (pintype "bidirectional"))
      (node (ref "U1") (pin "P120") (pinfunction "VCCAUX2_P120") (pintype "passive"))
      (node (ref "U1") (pin "P134") (pinfunction "VCCAUX3_P134") (pintype "passive"))
      (node (ref "U1") (pin "P48") (pinfunction "VCCAUX0_P48") (pintype "passive"))
      (node (ref "U1") (pin "P62") (pinfunction "VCCAUX1_P62") (pintype "passive"))
    )
    (net (code "52") (name "/VCCINT") (class "Default")
      (node (ref "C22") (pin "1") (pinfunction "1_1") (pintype "passive"))
      (node (ref "C23") (pin "1") (pinfunction "1_1") (pintype "passive"))
      (node (ref "C24") (pin "1") (pinfunction "1_1") (pintype "passive"))
      (node (ref "C25") (pin "1") (pinfunction "1_1") (pintype "passive"))
      (node (ref "REG1.2") (pin "4") (pinfunction "VOUT1_4") (pintype "bidirectional"))
      (node (ref "U1") (pin "P121") (pinfunction "VCCINT2_P121") (pintype "passive"))
      (node (ref "U1") (pin "P133") (pinfunction "VCCINT3_P133") (pintype "passive"))
      (node (ref "U1") (pin "P49") (pinfunction "VCCINT0_P49") (pintype "passive"))
      (node (ref "U1") (pin "P61") (pinfunction "VCCINT1_P61") (pintype "passive"))
    )
    (net (code "53") (name "/VCC_B3") (class "Default")
      (node (ref "R11") (pin "2") (pinfunction "2_2") (pintype "passive"))
    )
    (net (code "54") (name "/X6") (class "Default")
      (node (ref "U1") (pin "P51") (pinfunction "IO_L31N_5D4_P51") (pintype "bidirectional"))
    )
    (net (code "57") (name "/XXCSYNC") (class "Default")
      (node (ref "U1") (pin "P137") (pinfunction "IO_L27N_0_P137") (pintype "bidirectional"))
    )
    (net (code "59") (name "GND") (class "Default")
      (node (ref "C1") (pin "1") (pinfunction "1_1") (pintype "passive"))
      (node (ref "C10") (pin "2") (pinfunction "2_2") (pintype "passive"))
      (node (ref "C11") (pin "2") (pinfunction "2_2") (pintype "passive"))
      (node (ref "C12") (pin "2") (pinfunction "2_2") (pintype "passive"))
      (node (ref "C13") (pin "2") (pinfunction "2_2") (pintype "passive"))
      (node (ref "C14") (pin "2") (pinfunction "2_2") (pintype "passive"))
      (node (ref "C15") (pin "2") (pinfunction "2_2") (pintype "passive"))
      (node (ref "C16") (pin "2") (pinfunction "2_2") (pintype "passive"))
      (node (ref "C17") (pin "2") (pinfunction "2_2") (pintype "passive"))
      (node (ref "C18") (pin "2") (pinfunction "2_2") (pintype "passive"))
      (node (ref "C19") (pin "2") (pinfunction "2_2") (pintype "passive"))
      (node (ref "C20") (pin "2") (pinfunction "2_2") (pintype "passive"))
      (node (ref "C21") (pin "2") (pinfunction "2_2") (pintype "passive"))
      (node (ref "C22") (pin "2") (pinfunction "2_2") (pintype "passive"))
      (node (ref "C23") (pin "2") (pinfunction "2_2") (pintype "passive"))
      (node (ref "C24") (pin "2") (pinfunction "2_2") (pintype "passive"))
      (node (ref "C25") (pin "2") (pinfunction "2_2") (pintype "passive"))
      (node (ref "C26") (pin "2") (pinfunction "2_2") (pintype "passive"))
      (node (ref "C27") (pin "2") (pinfunction "2_2") (pintype "passive"))
      (node (ref "C28") (pin "2") (pinfunction "2_2") (pintype "passive"))
      (node (ref "C29") (pin "2") (pinfunction "2_2") (pintype "passive"))
      (node (ref "C30") (pin "2") (pinfunction "2_2") (pintype "passive"))
      (node (ref "C31") (pin "2") (pinfunction "2_2") (pintype "passive"))
      (node (ref "C32") (pin "2") (pinfunction "2_2") (pintype "passive"))
      (node (ref "C33") (pin "-") (pinfunction "-_-") (pintype "passive"))
      (node (ref "C34") (pin "2") (pinfunction "2_2") (pintype "passive"))
      (node (ref "C5") (pin "1") (pinfunction "1_1") (pintype "passive"))
      (node (ref "C6") (pin "2") (pinfunction "2_2") (pintype "passive"))
      (node (ref "C7") (pin "2") (pinfunction "2_2") (pintype "passive"))
      (node (ref "C8") (pin "2") (pinfunction "2_2") (pintype "passive"))
      (node (ref "C9") (pin "2") (pinfunction "2_2") (pintype "passive"))
      (node (ref "IC1") (pin "11") (pinfunction "GND_11") (pintype "bidirectional"))
      (node (ref "IC2") (pin "4") (pinfunction "GND_4") (pintype "power_in"))
      (node (ref "IC3") (pin "3") (pinfunction "GND_3") (pintype "bidirectional"))
      (node (ref "JP3") (pin "6") (pinfunction "6_6") (pintype "passive"))
      (node (ref "R12") (pin "1") (pinfunction "1_1") (pintype "passive"))
      (node (ref "R17") (pin "1") (pinfunction "1_1") (pintype "passive"))
      (node (ref "R19") (pin "1") (pinfunction "1_1") (pintype "passive"))
      (node (ref "R21") (pin "1") (pinfunction "1_1") (pintype "passive"))
      (node (ref "REG1.2") (pin "1") (pinfunction "GND_1") (pintype "bidirectional"))
      (node (ref "REG2.5") (pin "1") (pinfunction "GND_1") (pintype "bidirectional"))
      (node (ref "RESET_SW") (pin "2") (pinfunction "2_2") (pintype "passive"))
      (node (ref "U$1") (pin "P24") (pinfunction "VSS_P24") (pintype "bidirectional"))
      (node (ref "U$1") (pin "P30") (pinfunction "CE_P30") (pintype "bidirectional"))
      (node (ref "U$2") (pin "GND") (pinfunction "GND_GND") (pintype "power_in"))
      (node (ref "U$4") (pin "1") (pinfunction "GND_1") (pintype "bidirectional"))
      (node (ref "U$6") (pin "P24") (pinfunction "VSS_P24") (pintype "bidirectional"))
      (node (ref "U$6") (pin "P30") (pinfunction "CE_P30") (pintype "bidirectional"))
      (node (ref "U1") (pin "P101") (pinfunction "GND11_P101") (pintype "passive"))
      (node (ref "U1") (pin "P114") (pinfunction "GND12_P114") (pintype "passive"))
      (node (ref "U1") (pin "P117") (pinfunction "GND13_P117") (pintype "passive"))
      (node (ref "U1") (pin "P136") (pinfunction "GND14_P136") (pintype "passive"))
      (node (ref "U1") (pin "P139") (pinfunction "GND15_P139") (pintype "passive"))
      (node (ref "U1") (pin "P16") (pinfunction "GND1_P16") (pintype "passive"))
      (node (ref "U1") (pin "P22") (pinfunction "GND2_P22") (pintype "passive"))
      (node (ref "U1") (pin "P29") (pinfunction "GND3_P29") (pintype "passive"))
      (node (ref "U1") (pin "P37") (pinfunction "M1_P37") (pintype "bidirectional"))
      (node (ref "U1") (pin "P38") (pinfunction "M0_P38") (pintype "bidirectional"))
      (node (ref "U1") (pin "P39") (pinfunction "M2_P39") (pintype "bidirectional"))
      (node (ref "U1") (pin "P42") (pinfunction "GND4_P42") (pintype "passive"))
      (node (ref "U1") (pin "P45") (pinfunction "GND5_P45") (pintype "passive"))
      (node (ref "U1") (pin "P64") (pinfunction "GND6_P64") (pintype "passive"))
      (node (ref "U1") (pin "P67") (pinfunction "GND7_P67") (pintype "passive"))
      (node (ref "U1") (pin "P81") (pinfunction "GND8_P81") (pintype "passive"))
      (node (ref "U1") (pin "P88") (pinfunction "GND9_P88") (pintype "passive"))
      (node (ref "U1") (pin "P9") (pinfunction "GND0_P9") (pintype "passive"))
      (node (ref "U1") (pin "P94") (pinfunction "GND10_P94") (pintype "passive"))
      (node (ref "X1") (pin "3") (pinfunction "2_3") (pintype "passive"))
      (node (ref "X2") (pin "13") (pinfunction "13_13") (pintype "passive"))
      (node (ref "X2") (pin "14") (pinfunction "14_14") (pintype "passive"))
      (node (ref "X2") (pin "17") (pinfunction "17_17") (pintype "passive"))
      (node (ref "X2") (pin "18") (pinfunction "18_18") (pintype "passive"))
      (node (ref "X2") (pin "21") (pinfunction "21_21") (pintype "passive"))
      (node (ref "X2") (pin "4") (pinfunction "4_4") (pintype "passive"))
      (node (ref "X2") (pin "5") (pinfunction "5_5") (pintype "passive"))
      (node (ref "X2") (pin "9") (pinfunction "9_9") (pintype "passive"))
      (node (ref "X3") (pin "3") (pinfunction "3_3") (pintype "passive"))
      (node (ref "X3") (pin "SH1") (pinfunction "PE1_SH1") (pintype "power_in"))
      (node (ref "X3") (pin "SH2") (pinfunction "PE2_SH2") (pintype "power_in"))
      (node (ref "X3") (pin "SH3") (pinfunction "PE3_SH3") (pintype "power_in"))
      (node (ref "X4") (pin "8") (pinfunction "F_8") (pintype "passive"))
      (node (ref "X4") (pin "G1") (pinfunction "G1_G1") (pintype "passive"))
      (node (ref "X5") (pin "8") (pinfunction "F_8") (pintype "passive"))
      (node (ref "X5") (pin "G1") (pinfunction "G1_G1") (pintype "passive"))
      (node (ref "X8") (pin "1") (pinfunction "1_1") (pintype "power_in"))
      (node (ref "X8") (pin "3") (pinfunction "3_3") (pintype "power_in"))
    )
    (net (code "60") (name "Net-(C1-Pad2)") (class "Default")
      (node (ref "C1") (pin "2") (pinfunction "2_2") (pintype "passive"))
      (node (ref "R23") (pin "2") (pinfunction "2_2") (pintype "passive"))
      (node (ref "R48") (pin "1") (pinfunction "1_1") (pintype "passive"))
    )
    (net (code "61") (name "Net-(C2-Pad1)") (class "Default")
      (node (ref "C2") (pin "1") (pinfunction "1_1") (pintype "passive"))
      (node (ref "R17") (pin "2") (pinfunction "2_2") (pintype "passive"))
      (node (ref "X1") (pin "1") (pinfunction "1_1") (pintype "passive"))
    )
    (net (code "62") (name "Net-(C3-Pad1)") (class "Default")
      (node (ref "C3") (pin "1") (pinfunction "1_1") (pintype "passive"))
      (node (ref "R48") (pin "2") (pinfunction "2_2") (pintype "passive"))
    )
    (net (code "63") (name "Net-(C4-Pad1)") (class "Default")
      (node (ref "C4") (pin "1") (pinfunction "1_1") (pintype "passive"))
      (node (ref "R49") (pin "2") (pinfunction "2_2") (pintype "passive"))
    )
    (net (code "64") (name "Net-(C5-Pad2)") (class "Default")
      (node (ref "C5") (pin "2") (pinfunction "2_2") (pintype "passive"))
      (node (ref "R34") (pin "2") (pinfunction "2_2") (pintype "passive"))
      (node (ref "R49") (pin "1") (pinfunction "1_1") (pintype "passive"))
    )
    (net (code "65") (name "Net-(IC1-CLK)") (class "Default")
      (node (ref "IC1") (pin "3") (pinfunction "CLK_3") (pintype "bidirectional"))
      (node (ref "U1") (pin "P72") (pinfunction "CCLK_P72") (pintype "bidirectional"))
    )
    (net (code "66") (name "Net-(IC1-TDI)") (class "Default")
      (node (ref "IC1") (pin "4") (pinfunction "TDI_4") (pintype "bidirectional"))
      (node (ref "U1") (pin "P109") (pinfunction "TDO_P109") (pintype "bidirectional"))
    )
    (net (code "67") (name "Net-(IC1-{slash}CE)") (class "Default")
      (node (ref "IC1") (pin "10") (pinfunction "/CE_10") (pintype "bidirectional"))
      (node (ref "U1") (pin "P71") (pinfunction "DONE_P71") (pintype "bidirectional"))
    )
    (net (code "68") (name "Net-(IC1-{slash}CF)") (class "Default")
      (node (ref "IC1") (pin "7") (pinfunction "/CF_7") (pintype "bidirectional"))
      (node (ref "U1") (pin "P143") (pinfunction "PROG_B_P143") (pintype "bidirectional"))
    )
    (net (code "69") (name "Net-(IC3-D+)") (class "Default")
      (node (ref "IC3") (pin "29") (pinfunction "D+_29") (pintype "bidirectional"))
      (node (ref "R54") (pin "2") (pinfunction "2_2") (pintype "passive"))
    )
    (net (code "70") (name "Net-(IC3-D-)") (class "Default")
      (node (ref "IC3") (pin "30") (pinfunction "D-_30") (pintype "bidirectional"))
      (node (ref "R53") (pin "2") (pinfunction "2_2") (pintype "passive"))
    )
    (net (code "71") (name "Net-(IC3-UGND)") (class "Default")
      (node (ref "IC3") (pin "28") (pinfunction "UGND_28") (pintype "bidirectional"))
      (node (ref "X6") (pin "4") (pinfunction "4_4") (pintype "passive"))
    )
    (net (code "72") (name "Net-(Q5-B)") (class "Default")
      (node (ref "Q5") (pin "1") (pinfunction "B_1") (pintype "passive"))
      (node (ref "R8") (pin "2") (pinfunction "2_2") (pintype "passive"))
    )
    (net (code "73") (name "Net-(Q5-E)") (class "Default")
      (node (ref "Q5") (pin "2") (pinfunction "E_2") (pintype "passive"))
      (node (ref "R13") (pin "2") (pinfunction "2_2") (pintype "passive"))
      (node (ref "R14") (pin "2") (pinfunction "2_2") (pintype "passive"))
    )
    (net (code "74") (name "Net-(Q6-B)") (class "Default")
      (node (ref "Q6") (pin "1") (pinfunction "B_1") (pintype "passive"))
      (node (ref "R10") (pin "2") (pinfunction "2_2") (pintype "passive"))
      (node (ref "R9") (pin "2") (pinfunction "2_2") (pintype "passive"))
    )
    (net (code "75") (name "Net-(Q6-E)") (class "Default")
      (node (ref "Q6") (pin "2") (pinfunction "E_2") (pintype "passive"))
      (node (ref "R15") (pin "2") (pinfunction "2_2") (pintype "passive"))
      (node (ref "R16") (pin "2") (pinfunction "2_2") (pintype "passive"))
      (node (ref "R20") (pin "2") (pinfunction "2_2") (pintype "passive"))
    )
    (net (code "76") (name "Net-(Q7-B)") (class "Default")
      (node (ref "Q7") (pin "1") (pinfunction "B_1") (pintype "passive"))
      (node (ref "R29") (pin "2") (pinfunction "2_2") (pintype "passive"))
      (node (ref "R30") (pin "2") (pinfunction "2_2") (pintype "passive"))
    )
    (net (code "77") (name "Net-(Q7-E)") (class "Default")
      (node (ref "Q7") (pin "2") (pinfunction "E_2") (pintype "passive"))
      (node (ref "R31") (pin "2") (pinfunction "2_2") (pintype "passive"))
      (node (ref "R32") (pin "2") (pinfunction "2_2") (pintype "passive"))
      (node (ref "R33") (pin "2") (pinfunction "2_2") (pintype "passive"))
    )
    (net (code "78") (name "Net-(Q8-B)") (class "Default")
      (node (ref "Q8") (pin "1") (pinfunction "B_1") (pintype "passive"))
      (node (ref "R24") (pin "2") (pinfunction "2_2") (pintype "passive"))
      (node (ref "R25") (pin "2") (pinfunction "2_2") (pintype "passive"))
    )
    (net (code "79") (name "Net-(Q8-E)") (class "Default")
      (node (ref "Q8") (pin "2") (pinfunction "E_2") (pintype "passive"))
      (node (ref "R26") (pin "2") (pinfunction "2_2") (pintype "passive"))
      (node (ref "R27") (pin "2") (pinfunction "2_2") (pintype "passive"))
      (node (ref "R28") (pin "2") (pinfunction "2_2") (pintype "passive"))
    )
    (net (code "80") (name "Net-(R18-Pad2)") (class "Default")
      (node (ref "R18") (pin "2") (pinfunction "2_2") (pintype "passive"))
      (node (ref "R22") (pin "2") (pinfunction "2_2") (pintype "passive"))
    )
    (net (code "81") (name "Net-(R53-Pad1)") (class "Default")
      (node (ref "R53") (pin "1") (pinfunction "1_1") (pintype "passive"))
      (node (ref "X6") (pin "2") (pinfunction "2_2") (pintype "passive"))
    )
    (net (code "82") (name "Net-(R54-Pad1)") (class "Default")
      (node (ref "R54") (pin "1") (pinfunction "1_1") (pintype "passive"))
      (node (ref "X6") (pin "3") (pinfunction "3_3") (pintype "passive"))
    )
    (net (code "83") (name "Net-(T2-B)") (class "Default")
      (node (ref "C2") (pin "2") (pinfunction "2_2") (pintype "passive"))
      (node (ref "R18") (pin "1") (pinfunction "1_1") (pintype "passive"))
      (node (ref "R19") (pin "2") (pinfunction "2_2") (pintype "passive"))
      (node (ref "T2") (pin "1") (pinfunction "B_1") (pintype "passive"))
    )
    (net (code "84") (name "Net-(U$1-A0)") (class "Default")
      (node (ref "U$1") (pin "P20") (pinfunction "A0_P20") (pintype "bidirectional"))
      (node (ref "U1") (pin "P77") (pinfunction "IO_L20P_3_P77") (pintype "bidirectional"))
    )
    (net (code "85") (name "Net-(U$1-A1)") (class "Default")
      (node (ref "U$1") (pin "P19") (pinfunction "A1_P19") (pintype "bidirectional"))
      (node (ref "U1") (pin "P76") (pinfunction "IO_P76") (pintype "bidirectional"))
    )
    (net (code "86") (name "Net-(U$1-A2)") (class "Default")
      (node (ref "U$1") (pin "P18") (pinfunction "A2_P18") (pintype "bidirectional"))
      (node (ref "U1") (pin "P74") (pinfunction "IO_L01N_3VRP_3_P74") (pintype "bidirectional"))
    )
    (net (code "87") (name "Net-(U$1-A3)") (class "Default")
      (node (ref "U$1") (pin "P17") (pinfunction "A3_P17") (pintype "bidirectional"))
      (node (ref "U1") (pin "P73") (pinfunction "IO_L01P_3VRN_3_P73") (pintype "bidirectional"))
    )
    (net (code "88") (name "Net-(U$1-A4)") (class "Default")
      (node (ref "U$1") (pin "P16") (pinfunction "A4_P16") (pintype "bidirectional"))
      (node (ref "U1") (pin "P108") (pinfunction "IO_L01N_2VRP_2_P108") (pintype "bidirectional"))
    )
    (net (code "89") (name "Net-(U$1-A5)") (class "Default")
      (node (ref "U$1") (pin "P15") (pinfunction "A5_P15") (pintype "bidirectional"))
      (node (ref "U1") (pin "P107") (pinfunction "IO_L01P_2VRN_2_P107") (pintype "bidirectional"))
    )
    (net (code "90") (name "Net-(U$1-A6)") (class "Default")
      (node (ref "U$1") (pin "P14") (pinfunction "A6_P14") (pintype "bidirectional"))
      (node (ref "U1") (pin "P105") (pinfunction "IO_L20N_2_P105") (pintype "bidirectional"))
    )
    (net (code "91") (name "Net-(U$1-A7)") (class "Default")
      (node (ref "U$1") (pin "P13") (pinfunction "A7_P13") (pintype "bidirectional"))
      (node (ref "U1") (pin "P104") (pinfunction "IO_L20P_2_P104") (pintype "bidirectional"))
    )
    (net (code "92") (name "Net-(U$1-A8)") (class "Default")
      (node (ref "U$1") (pin "P3") (pinfunction "A8_P3") (pintype "bidirectional"))
      (node (ref "U1") (pin "P93") (pinfunction "IO_L40N_2_P93") (pintype "bidirectional"))
    )
    (net (code "93") (name "Net-(U$1-A9)") (class "Default")
      (node (ref "U$1") (pin "P2") (pinfunction "A9_P2") (pintype "bidirectional"))
      (node (ref "U1") (pin "P92") (pinfunction "IO_L40P_2VREF_2_P92") (pintype "bidirectional"))
    )
    (net (code "94") (name "Net-(U$1-A10)") (class "Default")
      (node (ref "U$1") (pin "P31") (pinfunction "A10_P31") (pintype "bidirectional"))
      (node (ref "U1") (pin "P87") (pinfunction "IO_L24N_3_P87") (pintype "bidirectional"))
    )
    (net (code "95") (name "Net-(U$1-A11)") (class "Default")
      (node (ref "U$1") (pin "P1") (pinfunction "A11_P1") (pintype "bidirectional"))
      (node (ref "U1") (pin "P90") (pinfunction "IO_L40N_3VREF_3_P90") (pintype "bidirectional"))
    )
    (net (code "96") (name "Net-(U$1-A12)") (class "Default")
      (node (ref "U$1") (pin "P12") (pinfunction "A12_P12") (pintype "bidirectional"))
      (node (ref "U1") (pin "P103") (pinfunction "IO_L21N_2_P103") (pintype "bidirectional"))
    )
    (net (code "97") (name "Net-(U$1-A13)") (class "Default")
      (node (ref "U$1") (pin "P4") (pinfunction "A13_P4") (pintype "bidirectional"))
      (node (ref "U1") (pin "P95") (pinfunction "IO_L24P_2_P95") (pintype "bidirectional"))
    )
    (net (code "98") (name "Net-(U$1-A14)") (class "Default")
      (node (ref "U$1") (pin "P11") (pinfunction "A14_P11") (pintype "bidirectional"))
      (node (ref "U1") (pin "P102") (pinfunction "IO_L21P_2_P102") (pintype "bidirectional"))
    )
    (net (code "99") (name "Net-(U$1-A15)") (class "Default")
      (node (ref "U$1") (pin "P7") (pinfunction "A15_P7") (pintype "bidirectional"))
      (node (ref "U1") (pin "P98") (pinfunction "IO_L23N_2VREF_2_P98") (pintype "bidirectional"))
    )
    (net (code "100") (name "Net-(U$1-A16)") (class "Default")
      (node (ref "U$1") (pin "P10") (pinfunction "A16_P10") (pintype "bidirectional"))
      (node (ref "U1") (pin "P100") (pinfunction "IO_L22N_2_P100") (pintype "bidirectional"))
    )
    (net (code "101") (name "Net-(U$1-A17)") (class "Default")
      (node (ref "U$1") (pin "P6") (pinfunction "A17_P6") (pintype "bidirectional"))
      (node (ref "U1") (pin "P97") (pinfunction "IO_L23P_2_P97") (pintype "bidirectional"))
    )
    (net (code "102") (name "Net-(U$1-A18)") (class "Default")
      (node (ref "U$1") (pin "P9") (pinfunction "A18_P9") (pintype "bidirectional"))
      (node (ref "U1") (pin "P99") (pinfunction "IO_L22P_2_P99") (pintype "bidirectional"))
    )
    (net (code "103") (name "Net-(U$1-DQ0)") (class "Default")
      (node (ref "U$1") (pin "P21") (pinfunction "DQ0_P21") (pintype "bidirectional"))
      (node (ref "U1") (pin "P78") (pinfunction "IO_L20N_3_P78") (pintype "bidirectional"))
    )
    (net (code "104") (name "Net-(U$1-DQ1)") (class "Default")
      (node (ref "U$1") (pin "P22") (pinfunction "DQ1_P22") (pintype "bidirectional"))
      (node (ref "U1") (pin "P79") (pinfunction "IO_L21P_3_P79") (pintype "bidirectional"))
    )
    (net (code "105") (name "Net-(U$1-DQ2)") (class "Default")
      (node (ref "U$1") (pin "P23") (pinfunction "DQ2_P23") (pintype "bidirectional"))
      (node (ref "U1") (pin "P80") (pinfunction "IO_L21N_3_P80") (pintype "bidirectional"))
    )
    (net (code "106") (name "Net-(U$1-DQ3)") (class "Default")
      (node (ref "U$1") (pin "P25") (pinfunction "DQ3_P25") (pintype "bidirectional"))
      (node (ref "U1") (pin "P82") (pinfunction "IO_L22P_3_P82") (pintype "bidirectional"))
    )
    (net (code "107") (name "Net-(U$1-DQ4)") (class "Default")
      (node (ref "U$1") (pin "P26") (pinfunction "DQ4_P26") (pintype "bidirectional"))
      (node (ref "U1") (pin "P83") (pinfunction "IO_L22N_3_P83") (pintype "bidirectional"))
    )
    (net (code "108") (name "Net-(U$1-DQ5)") (class "Default")
      (node (ref "U$1") (pin "P27") (pinfunction "DQ5_P27") (pintype "bidirectional"))
      (node (ref "U1") (pin "P84") (pinfunction "IO_L23P_3VREF_3_P84") (pintype "bidirectional"))
    )
    (net (code "109") (name "Net-(U$1-DQ6)") (class "Default")
      (node (ref "U$1") (pin "P28") (pinfunction "DQ6_P28") (pintype "bidirectional"))
      (node (ref "U1") (pin "P85") (pinfunction "IO_L23N_3_P85") (pintype "bidirectional"))
    )
    (net (code "110") (name "Net-(U$1-DQ7)") (class "Default")
      (node (ref "U$1") (pin "P29") (pinfunction "DQ7_P29") (pintype "bidirectional"))
      (node (ref "U1") (pin "P86") (pinfunction "IO_L24P_3_P86") (pintype "bidirectional"))
    )
    (net (code "111") (name "Net-(U$1-OE)") (class "Default")
      (node (ref "U$1") (pin "P32") (pinfunction "OE_P32") (pintype "bidirectional"))
      (node (ref "U1") (pin "P89") (pinfunction "IO_L40P_3_P89") (pintype "bidirectional"))
    )
    (net (code "112") (name "Net-(U$1-WE)") (class "Default")
      (node (ref "U$1") (pin "P5") (pinfunction "WE_P5") (pintype "bidirectional"))
      (node (ref "U1") (pin "P96") (pinfunction "IO_L24N_2_P96") (pintype "bidirectional"))
    )
    (net (code "113") (name "Net-(U$6-A0)") (class "Default")
      (node (ref "U$6") (pin "P20") (pinfunction "A0_P20") (pintype "bidirectional"))
      (node (ref "U1") (pin "P24") (pinfunction "IO_L24N_6VREF_6_P24") (pintype "bidirectional"))
    )
    (net (code "114") (name "Net-(U$6-A1)") (class "Default")
      (node (ref "U$6") (pin "P19") (pinfunction "A1_P19") (pintype "bidirectional"))
      (node (ref "U1") (pin "P23") (pinfunction "IO_L24P_6_P23") (pintype "bidirectional"))
    )
    (net (code "115") (name "Net-(U$6-A2)") (class "Default")
      (node (ref "U$6") (pin "P18") (pinfunction "A2_P18") (pintype "bidirectional"))
      (node (ref "U1") (pin "P21") (pinfunction "IO_L40N_6_P21") (pintype "bidirectional"))
    )
    (net (code "116") (name "Net-(U$6-A3)") (class "Default")
      (node (ref "U$6") (pin "P17") (pinfunction "A3_P17") (pintype "bidirectional"))
      (node (ref "U1") (pin "P20") (pinfunction "IO_L40P_6VREF_6_P20") (pintype "bidirectional"))
    )
    (net (code "117") (name "Net-(U$6-A4)") (class "Default")
      (node (ref "U$6") (pin "P16") (pinfunction "A4_P16") (pintype "bidirectional"))
      (node (ref "U1") (pin "P18") (pinfunction "IO_L40N_7VREF_7_P18") (pintype "bidirectional"))
    )
    (net (code "118") (name "Net-(U$6-A5)") (class "Default")
      (node (ref "U$6") (pin "P15") (pinfunction "A5_P15") (pintype "bidirectional"))
      (node (ref "U1") (pin "P17") (pinfunction "IO_L40P_7_P17") (pintype "bidirectional"))
    )
    (net (code "119") (name "Net-(U$6-A6)") (class "Default")
      (node (ref "U$6") (pin "P14") (pinfunction "A6_P14") (pintype "bidirectional"))
      (node (ref "U1") (pin "P15") (pinfunction "IO_L24N_7_P15") (pintype "bidirectional"))
    )
    (net (code "120") (name "Net-(U$6-A7)") (class "Default")
      (node (ref "U$6") (pin "P13") (pinfunction "A7_P13") (pintype "bidirectional"))
      (node (ref "U1") (pin "P14") (pinfunction "IO_L24P_7_P14") (pintype "bidirectional"))
    )
    (net (code "121") (name "Net-(U$6-A8)") (class "Default")
      (node (ref "U$6") (pin "P3") (pinfunction "A8_P3") (pintype "bidirectional"))
      (node (ref "U1") (pin "P4") (pinfunction "IOVREF_7_P4") (pintype "bidirectional"))
    )
    (net (code "122") (name "Net-(U$6-A9)") (class "Default")
      (node (ref "U$6") (pin "P2") (pinfunction "A9_P2") (pintype "bidirectional"))
      (node (ref "U1") (pin "P2") (pinfunction "IO_L01N_7VRP_7_P2") (pintype "bidirectional"))
    )
    (net (code "123") (name "Net-(U$6-A10)") (class "Default")
      (node (ref "U$6") (pin "P31") (pinfunction "A10_P31") (pintype "bidirectional"))
      (node (ref "U1") (pin "P35") (pinfunction "IO_L01P_6VRN_6_P35") (pintype "bidirectional"))
    )
    (net (code "124") (name "Net-(U$6-A11)") (class "Default")
      (node (ref "U$6") (pin "P1") (pinfunction "A11_P1") (pintype "bidirectional"))
      (node (ref "U1") (pin "P1") (pinfunction "IO_L01P_7VRN_7_P1") (pintype "bidirectional"))
    )
    (net (code "125") (name "Net-(U$6-A12)") (class "Default")
      (node (ref "U$6") (pin "P12") (pinfunction "A12_P12") (pintype "bidirectional"))
      (node (ref "U1") (pin "P13") (pinfunction "IO_L23N_7_P13") (pintype "bidirectional"))
    )
    (net (code "126") (name "Net-(U$6-A13)") (class "Default")
      (node (ref "U$6") (pin "P4") (pinfunction "A13_P4") (pintype "bidirectional"))
      (node (ref "U1") (pin "P5") (pinfunction "IO_L20P_7_P5") (pintype "bidirectional"))
    )
    (net (code "127") (name "Net-(U$6-A14)") (class "Default")
      (node (ref "U$6") (pin "P11") (pinfunction "A14_P11") (pintype "bidirectional"))
      (node (ref "U1") (pin "P12") (pinfunction "IO_L23P_7_P12") (pintype "bidirectional"))
    )
    (net (code "128") (name "Net-(U$6-A15)") (class "Default")
      (node (ref "U$6") (pin "P7") (pinfunction "A15_P7") (pintype "bidirectional"))
      (node (ref "U1") (pin "P8") (pinfunction "IO_L21N_7_P8") (pintype "bidirectional"))
    )
    (net (code "129") (name "Net-(U$6-A16)") (class "Default")
      (node (ref "U$6") (pin "P10") (pinfunction "A16_P10") (pintype "bidirectional"))
      (node (ref "U1") (pin "P11") (pinfunction "IO_L22N_7_P11") (pintype "bidirectional"))
    )
    (net (code "130") (name "Net-(U$6-A17)") (class "Default")
      (node (ref "U$6") (pin "P6") (pinfunction "A17_P6") (pintype "bidirectional"))
      (node (ref "U1") (pin "P7") (pinfunction "IO_L21P_7_P7") (pintype "bidirectional"))
    )
    (net (code "131") (name "Net-(U$6-A18)") (class "Default")
      (node (ref "U$6") (pin "P9") (pinfunction "A18_P9") (pintype "bidirectional"))
      (node (ref "U1") (pin "P10") (pinfunction "IO_L22P_7_P10") (pintype "bidirectional"))
    )
    (net (code "132") (name "Net-(U$6-DQ0)") (class "Default")
      (node (ref "U$6") (pin "P21") (pinfunction "DQ0_P21") (pintype "bidirectional"))
      (node (ref "U1") (pin "P25") (pinfunction "IO_L23P_6_P25") (pintype "bidirectional"))
    )
    (net (code "133") (name "Net-(U$6-DQ1)") (class "Default")
      (node (ref "U$6") (pin "P22") (pinfunction "DQ1_P22") (pintype "bidirectional"))
      (node (ref "U1") (pin "P26") (pinfunction "IO_L23N_6_P26") (pintype "bidirectional"))
    )
    (net (code "134") (name "Net-(U$6-DQ2)") (class "Default")
      (node (ref "U$6") (pin "P23") (pinfunction "DQ2_P23") (pintype "bidirectional"))
      (node (ref "U1") (pin "P27") (pinfunction "IO_L22P_6_P27") (pintype "bidirectional"))
    )
    (net (code "135") (name "Net-(U$6-DQ3)") (class "Default")
      (node (ref "U$6") (pin "P25") (pinfunction "DQ3_P25") (pintype "bidirectional"))
      (node (ref "U1") (pin "P28") (pinfunction "IO_L22N_6_P28") (pintype "bidirectional"))
    )
    (net (code "136") (name "Net-(U$6-DQ4)") (class "Default")
      (node (ref "U$6") (pin "P26") (pinfunction "DQ4_P26") (pintype "bidirectional"))
      (node (ref "U1") (pin "P30") (pinfunction "IO_L21P_6_P30") (pintype "bidirectional"))
    )
    (net (code "137") (name "Net-(U$6-DQ5)") (class "Default")
      (node (ref "U$6") (pin "P27") (pinfunction "DQ5_P27") (pintype "bidirectional"))
      (node (ref "U1") (pin "P31") (pinfunction "IO_L21N_6_P31") (pintype "bidirectional"))
    )
    (net (code "138") (name "Net-(U$6-DQ6)") (class "Default")
      (node (ref "U$6") (pin "P28") (pinfunction "DQ6_P28") (pintype "bidirectional"))
      (node (ref "U1") (pin "P32") (pinfunction "IO_L20P_6_P32") (pintype "bidirectional"))
    )
    (net (code "139") (name "Net-(U$6-DQ7)") (class "Default")
      (node (ref "U$6") (pin "P29") (pinfunction "DQ7_P29") (pintype "bidirectional"))
      (node (ref "U1") (pin "P33") (pinfunction "IO_L20N_6_P33") (pintype "bidirectional"))
    )
    (net (code "140") (name "Net-(U$6-OE)") (class "Default")
      (node (ref "U$6") (pin "P32") (pinfunction "OE_P32") (pintype "bidirectional"))
      (node (ref "U1") (pin "P36") (pinfunction "IO_L01N_6VRP_6_P36") (pintype "bidirectional"))
    )
    (net (code "141") (name "Net-(U$6-WE)") (class "Default")
      (node (ref "U$6") (pin "P5") (pinfunction "WE_P5") (pintype "bidirectional"))
      (node (ref "U1") (pin "P6") (pinfunction "IO_L20N_7_P6") (pintype "bidirectional"))
    )
    (net (code "142") (name "Net-(U1N-TCK)") (class "Default")
      (node (ref "R2") (pin "1") (pinfunction "1_1") (pintype "passive"))
      (node (ref "U1") (pin "P110") (pinfunction "TCK_P110") (pintype "bidirectional"))
    )
    (net (code "143") (name "Net-(U1N-TDI)") (class "Default")
      (node (ref "R1") (pin "1") (pinfunction "1_1") (pintype "passive"))
      (node (ref "U1") (pin "P144") (pinfunction "TDI_P144") (pintype "bidirectional"))
    )
    (net (code "144") (name "Net-(U1N-TMS)") (class "Default")
      (node (ref "R3") (pin "1") (pinfunction "1_1") (pintype "passive"))
      (node (ref "U1") (pin "P111") (pinfunction "TMS_P111") (pintype "bidirectional"))
    )
    (net (code "145") (name "Net-(X4A-F)") (class "Default")
      (node (ref "R40") (pin "2") (pinfunction "2_2") (pintype "passive"))
      (node (ref "X4") (pin "1") (pinfunction "F_1") (pintype "passive"))
    )
    (net (code "146") (name "Net-(X4B-F)") (class "Default")
      (node (ref "R41") (pin "2") (pinfunction "2_2") (pintype "passive"))
      (node (ref "X4") (pin "2") (pinfunction "F_2") (pintype "passive"))
    )
    (net (code "147") (name "Net-(X4C-F)") (class "Default")
      (node (ref "R42") (pin "2") (pinfunction "2_2") (pintype "passive"))
      (node (ref "X4") (pin "3") (pinfunction "F_3") (pintype "passive"))
    )
    (net (code "148") (name "Net-(X4D-F)") (class "Default")
      (node (ref "R43") (pin "2") (pinfunction "2_2") (pintype "passive"))
      (node (ref "X4") (pin "4") (pinfunction "F_4") (pintype "passive"))
    )
    (net (code "149") (name "Net-(X4F-F)") (class "Default")
      (node (ref "R44") (pin "2") (pinfunction "2_2") (pintype "passive"))
      (node (ref "X4") (pin "6") (pinfunction "F_6") (pintype "passive"))
    )
    (net (code "150") (name "Net-(X4G-F)") (class "Default")
      (node (ref "R45") (pin "2") (pinfunction "2_2") (pintype "passive"))
      (node (ref "X4") (pin "7") (pinfunction "F_7") (pintype "passive"))
    )
    (net (code "151") (name "Net-(X5A-F)") (class "Default")
      (node (ref "R46") (pin "1") (pinfunction "1_1") (pintype "passive"))
      (node (ref "X5") (pin "1") (pinfunction "F_1") (pintype "passive"))
    )
    (net (code "152") (name "Net-(X5B-F)") (class "Default")
      (node (ref "R39") (pin "1") (pinfunction "1_1") (pintype "passive"))
      (node (ref "X5") (pin "2") (pinfunction "F_2") (pintype "passive"))
    )
    (net (code "153") (name "Net-(X5C-F)") (class "Default")
      (node (ref "R38") (pin "1") (pinfunction "1_1") (pintype "passive"))
      (node (ref "X5") (pin "3") (pinfunction "F_3") (pintype "passive"))
    )
    (net (code "154") (name "Net-(X5D-F)") (class "Default")
      (node (ref "R37") (pin "1") (pinfunction "1_1") (pintype "passive"))
      (node (ref "X5") (pin "4") (pinfunction "F_4") (pintype "passive"))
    )
    (net (code "155") (name "Net-(X5F-F)") (class "Default")
      (node (ref "R36") (pin "1") (pinfunction "1_1") (pintype "passive"))
      (node (ref "X5") (pin "6") (pinfunction "F_6") (pintype "passive"))
    )
    (net (code "156") (name "Net-(X5G-F)") (class "Default")
      (node (ref "R35") (pin "1") (pinfunction "1_1") (pintype "passive"))
      (node (ref "X5") (pin "7") (pinfunction "F_7") (pintype "passive"))
    )
    (net (code "157") (name "unconnected-(IC1-NC.1-Pad2)") (class "Default")
      (node (ref "IC1") (pin "2") (pinfunction "NC.1_2") (pintype "bidirectional"))
    )
    (net (code "158") (name "unconnected-(IC1-NC.2-Pad9)") (class "Default")
      (node (ref "IC1") (pin "9") (pinfunction "NC.2_9") (pintype "bidirectional"))
    )
    (net (code "159") (name "unconnected-(IC1-NC.3-Pad12)") (class "Default")
      (node (ref "IC1") (pin "12") (pinfunction "NC.3_12") (pintype "bidirectional"))
    )
    (net (code "160") (name "unconnected-(IC1-NC.4-Pad14)") (class "Default")
      (node (ref "IC1") (pin "14") (pinfunction "NC.4_14") (pintype "bidirectional"))
    )
    (net (code "161") (name "unconnected-(IC1-NC.5-Pad15)") (class "Default")
      (node (ref "IC1") (pin "15") (pinfunction "NC.5_15") (pintype "bidirectional"))
    )
    (net (code "162") (name "unconnected-(IC1-NC.6-Pad16)") (class "Default")
      (node (ref "IC1") (pin "16") (pinfunction "NC.6_16") (pintype "bidirectional"))
    )
    (net (code "163") (name "unconnected-(IC1-{slash}CEO-Pad13)") (class "Default")
      (node (ref "IC1") (pin "13") (pinfunction "/CEO_13") (pintype "bidirectional"))
    )
    (net (code "164") (name "unconnected-(IC3-PC2(AIN2{slash}PCIN11)-Pad5)") (class "Default")
      (node (ref "IC3") (pin "5") (pinfunction "PC2(AIN2/PCIN11)_5") (pintype "bidirectional"))
    )
    (net (code "165") (name "unconnected-(IC3-PC4(PCINT10)-Pad26)") (class "Default")
      (node (ref "IC3") (pin "26") (pinfunction "PC4(PCINT10)_26") (pintype "bidirectional"))
    )
    (net (code "166") (name "unconnected-(IC3-PC5(OC1B{slash}PCINT9)-Pad25)") (class "Default")
      (node (ref "IC3") (pin "25") (pinfunction "PC5(OC1B/PCINT9)_25") (pintype "bidirectional"))
    )
    (net (code "167") (name "unconnected-(IC3-PC6(OC1A{slash}PCINT8)-Pad23)") (class "Default")
      (node (ref "IC3") (pin "23") (pinfunction "PC6(OC1A/PCINT8)_23") (pintype "bidirectional"))
    )
    (net (code "168") (name "unconnected-(IC3-PD0(INT0{slash}OC0B)-Pad6)") (class "Default")
      (node (ref "IC3") (pin "6") (pinfunction "PD0(INT0/OC0B)_6") (pintype "bidirectional"))
    )
    (net (code "169") (name "unconnected-(IC3-PD1(INT1{slash}AIN0)-Pad7)") (class "Default")
      (node (ref "IC3") (pin "7") (pinfunction "PD1(INT1/AIN0)_7") (pintype "bidirectional"))
    )
    (net (code "170") (name "unconnected-(IC3-PD4(INT5{slash}AIN3)-Pad10)") (class "Default")
      (node (ref "IC3") (pin "10") (pinfunction "PD4(INT5/AIN3)_10") (pintype "bidirectional"))
    )
    (net (code "171") (name "unconnected-(IC3-PD5(XCK{slash}AIN4{slash}PCINT12)-Pad11)") (class "Default")
      (node (ref "IC3") (pin "11") (pinfunction "PD5(XCK/AIN4/PCINT12)_11") (pintype "bidirectional"))
    )
    (net (code "172") (name "unconnected-(IC3-PD6(INT6{slash}AIN5{slash}RTS)-Pad12)") (class "Default")
      (node (ref "IC3") (pin "12") (pinfunction "PD6(INT6/AIN5/RTS)_12") (pintype "bidirectional"))
    )
    (net (code "173") (name "unconnected-(IC3-UCAP-Pad27)") (class "Default")
      (node (ref "IC3") (pin "27") (pinfunction "UCAP_27") (pintype "bidirectional"))
    )
    (net (code "174") (name "unconnected-(IC3-XTAL1-Pad1)") (class "Default")
      (node (ref "IC3") (pin "1") (pinfunction "XTAL1_1") (pintype "bidirectional"))
    )
    (net (code "175") (name "unconnected-(IC3-XTAL2{slash}PC0-Pad2)") (class "Default")
      (node (ref "IC3") (pin "2") (pinfunction "XTAL2/PC0_2") (pintype "bidirectional"))
    )
    (net (code "176") (name "unconnected-(IC3-{slash}RESET(PC1)-Pad24)") (class "Default")
      (node (ref "IC3") (pin "24") (pinfunction "/RESET(PC1)_24") (pintype "bidirectional"))
    )
    (net (code "177") (name "unconnected-(REG1.2-VOUT2-Pad2)") (class "Default")
      (node (ref "REG1.2") (pin "2") (pinfunction "VOUT2_2") (pintype "bidirectional"))
    )
    (net (code "178") (name "unconnected-(REG2.5-VOUT2-Pad2)") (class "Default")
      (node (ref "REG2.5") (pin "2") (pinfunction "VOUT2_2") (pintype "bidirectional"))
    )
    (net (code "179") (name "unconnected-(U$2-TRI-PadENA)") (class "Default")
      (node (ref "U$2") (pin "ENA") (pinfunction "TRI_ENA") (pintype "input"))
    )
    (net (code "180") (name "unconnected-(U$4-VOUT2-Pad2)") (class "Default")
      (node (ref "U$4") (pin "2") (pinfunction "VOUT2_2") (pintype "bidirectional"))
    )
    (net (code "181") (name "unconnected-(U$5-GND-Pad1)") (class "Default")
      (node (ref "U$5") (pin "1") (pinfunction "GND_1") (pintype "bidirectional"))
    )
    (net (code "182") (name "unconnected-(U$5-VCC-Pad4)") (class "Default")
      (node (ref "U$5") (pin "4") (pinfunction "VCC_4") (pintype "bidirectional"))
    )
    (net (code "183") (name "unconnected-(U$5-VOUT1-Pad2)") (class "Default")
      (node (ref "U$5") (pin "2") (pinfunction "VOUT1_2") (pintype "output"))
    )
    (net (code "184") (name "unconnected-(U$5-VOUT2-Pad3)") (class "Default")
      (node (ref "U$5") (pin "3") (pinfunction "VOUT2_3") (pintype "output"))
    )
    (net (code "185") (name "unconnected-(U$5-VOUT3-Pad6)") (class "Default")
      (node (ref "U$5") (pin "6") (pinfunction "VOUT3_6") (pintype "output"))
    )
    (net (code "186") (name "unconnected-(U$5-VOUT4-Pad7)") (class "Default")
      (node (ref "U$5") (pin "7") (pinfunction "VOUT4_7") (pintype "output"))
    )
    (net (code "187") (name "unconnected-(U1A-IO_L27P_0-PadP135)") (class "Default")
      (node (ref "U1") (pin "P135") (pinfunction "IO_L27P_0_P135") (pintype "bidirectional"))
    )
    (net (code "188") (name "unconnected-(U1A-IO_L30N_0-PadP132)") (class "Default")
      (node (ref "U1") (pin "P132") (pinfunction "IO_L30N_0_P132") (pintype "bidirectional"))
    )
    (net (code "189") (name "unconnected-(U1A-IO_L30P_0-PadP131)") (class "Default")
      (node (ref "U1") (pin "P131") (pinfunction "IO_L30P_0_P131") (pintype "bidirectional"))
    )
    (net (code "190") (name "unconnected-(U1A-IO_L31N_0-PadP130)") (class "Default")
      (node (ref "U1") (pin "P130") (pinfunction "IO_L31N_0_P130") (pintype "bidirectional"))
    )
    (net (code "191") (name "unconnected-(U1A-IO_L31P_0VREF_0-PadP129)") (class "Default")
      (node (ref "U1") (pin "P129") (pinfunction "IO_L31P_0VREF_0_P129") (pintype "bidirectional"))
    )
    (net (code "192") (name "unconnected-(U1A-IO_L32N_0GCLK7-PadP128)") (class "Default")
      (node (ref "U1") (pin "P128") (pinfunction "IO_L32N_0GCLK7_P128") (pintype "bidirectional"))
    )
    (net (code "193") (name "unconnected-(U1A-IO_L32P_0GCLK6-PadP127)") (class "Default")
      (node (ref "U1") (pin "P127") (pinfunction "IO_L32P_0GCLK6_P127") (pintype "bidirectional"))
    )
    (net (code "194") (name "unconnected-(U1C-IO-PadP116)") (class "Default")
      (node (ref "U1") (pin "P116") (pinfunction "IO_P116") (pintype "bidirectional"))
    )
    (net (code "195") (name "unconnected-(U1C-IO_L01N_1VRP_1-PadP113)") (class "Default")
      (node (ref "U1") (pin "P113") (pinfunction "IO_L01N_1VRP_1_P113") (pintype "bidirectional"))
    )
    (net (code "196") (name "unconnected-(U1C-IO_L01P_1VRN_1-PadP112)") (class "Default")
      (node (ref "U1") (pin "P112") (pinfunction "IO_L01P_1VRN_1_P112") (pintype "bidirectional"))
    )
    (net (code "197") (name "unconnected-(U1C-IO_L28N_1-PadP119)") (class "Default")
      (node (ref "U1") (pin "P119") (pinfunction "IO_L28N_1_P119") (pintype "bidirectional"))
    )
    (net (code "198") (name "unconnected-(U1C-IO_L28P_1-PadP118)") (class "Default")
      (node (ref "U1") (pin "P118") (pinfunction "IO_L28P_1_P118") (pintype "bidirectional"))
    )
    (net (code "199") (name "unconnected-(U1C-IO_L31N_1VREF_1-PadP123)") (class "Default")
      (node (ref "U1") (pin "P123") (pinfunction "IO_L31N_1VREF_1_P123") (pintype "bidirectional"))
    )
    (net (code "200") (name "unconnected-(U1C-IO_L31P_1-PadP122)") (class "Default")
      (node (ref "U1") (pin "P122") (pinfunction "IO_L31P_1_P122") (pintype "bidirectional"))
    )
    (net (code "201") (name "unconnected-(U1C-IO_L32N_1GCLK5-PadP125)") (class "Default")
      (node (ref "U1") (pin "P125") (pinfunction "IO_L32N_1GCLK5_P125") (pintype "bidirectional"))
    )
    (net (code "202") (name "unconnected-(U1C-IO_L32P_1GCLK4-PadP124)") (class "Default")
      (node (ref "U1") (pin "P124") (pinfunction "IO_L32P_1GCLK4_P124") (pintype "bidirectional"))
    )
    (net (code "203") (name "unconnected-(U1N-HSWAP_EN-PadP142)") (class "Default")
      (node (ref "U1") (pin "P142") (pinfunction "HSWAP_EN_P142") (pintype "bidirectional"))
    )
    (net (code "204") (name "unconnected-(X1-3-Pad2)") (class "Default")
      (node (ref "X1") (pin "2") (pinfunction "3_2") (pintype "passive"))
    )
    (net (code "205") (name "unconnected-(X2-Pad10)") (class "Default")
      (node (ref "X2") (pin "10") (pinfunction "10_10") (pintype "passive"))
    )
    (net (code "206") (name "unconnected-(X2-Pad12)") (class "Default")
      (node (ref "X2") (pin "12") (pinfunction "12_12") (pintype "passive"))
    )
    (net (code "207") (name "unconnected-(X3-Pad2)") (class "Default")
      (node (ref "X3") (pin "2") (pinfunction "2_2") (pintype "passive"))
    )
    (net (code "208") (name "unconnected-(X3-Pad8)") (class "Default")
      (node (ref "X3") (pin "8") (pinfunction "8_8") (pintype "passive"))
    )
    (net (code "209") (name "unconnected-(X4-PadG2)") (class "Default")
      (node (ref "X4") (pin "G2") (pinfunction "G2_G2") (pintype "passive"))
    )
    (net (code "210") (name "unconnected-(X5-PadG2)") (class "Default")
      (node (ref "X5") (pin "G2") (pinfunction "G2_G2") (pintype "passive"))
    )
    (net (code "211") (name "unconnected-(X6-Pad1)") (class "Default")
      (node (ref "X6") (pin "1") (pinfunction "1_1") (pintype "passive"))
    )
  )
)
